# XMICRO-SERIAL_V1_0.net
KiCad netlist of a schematic drawn in EAGLE
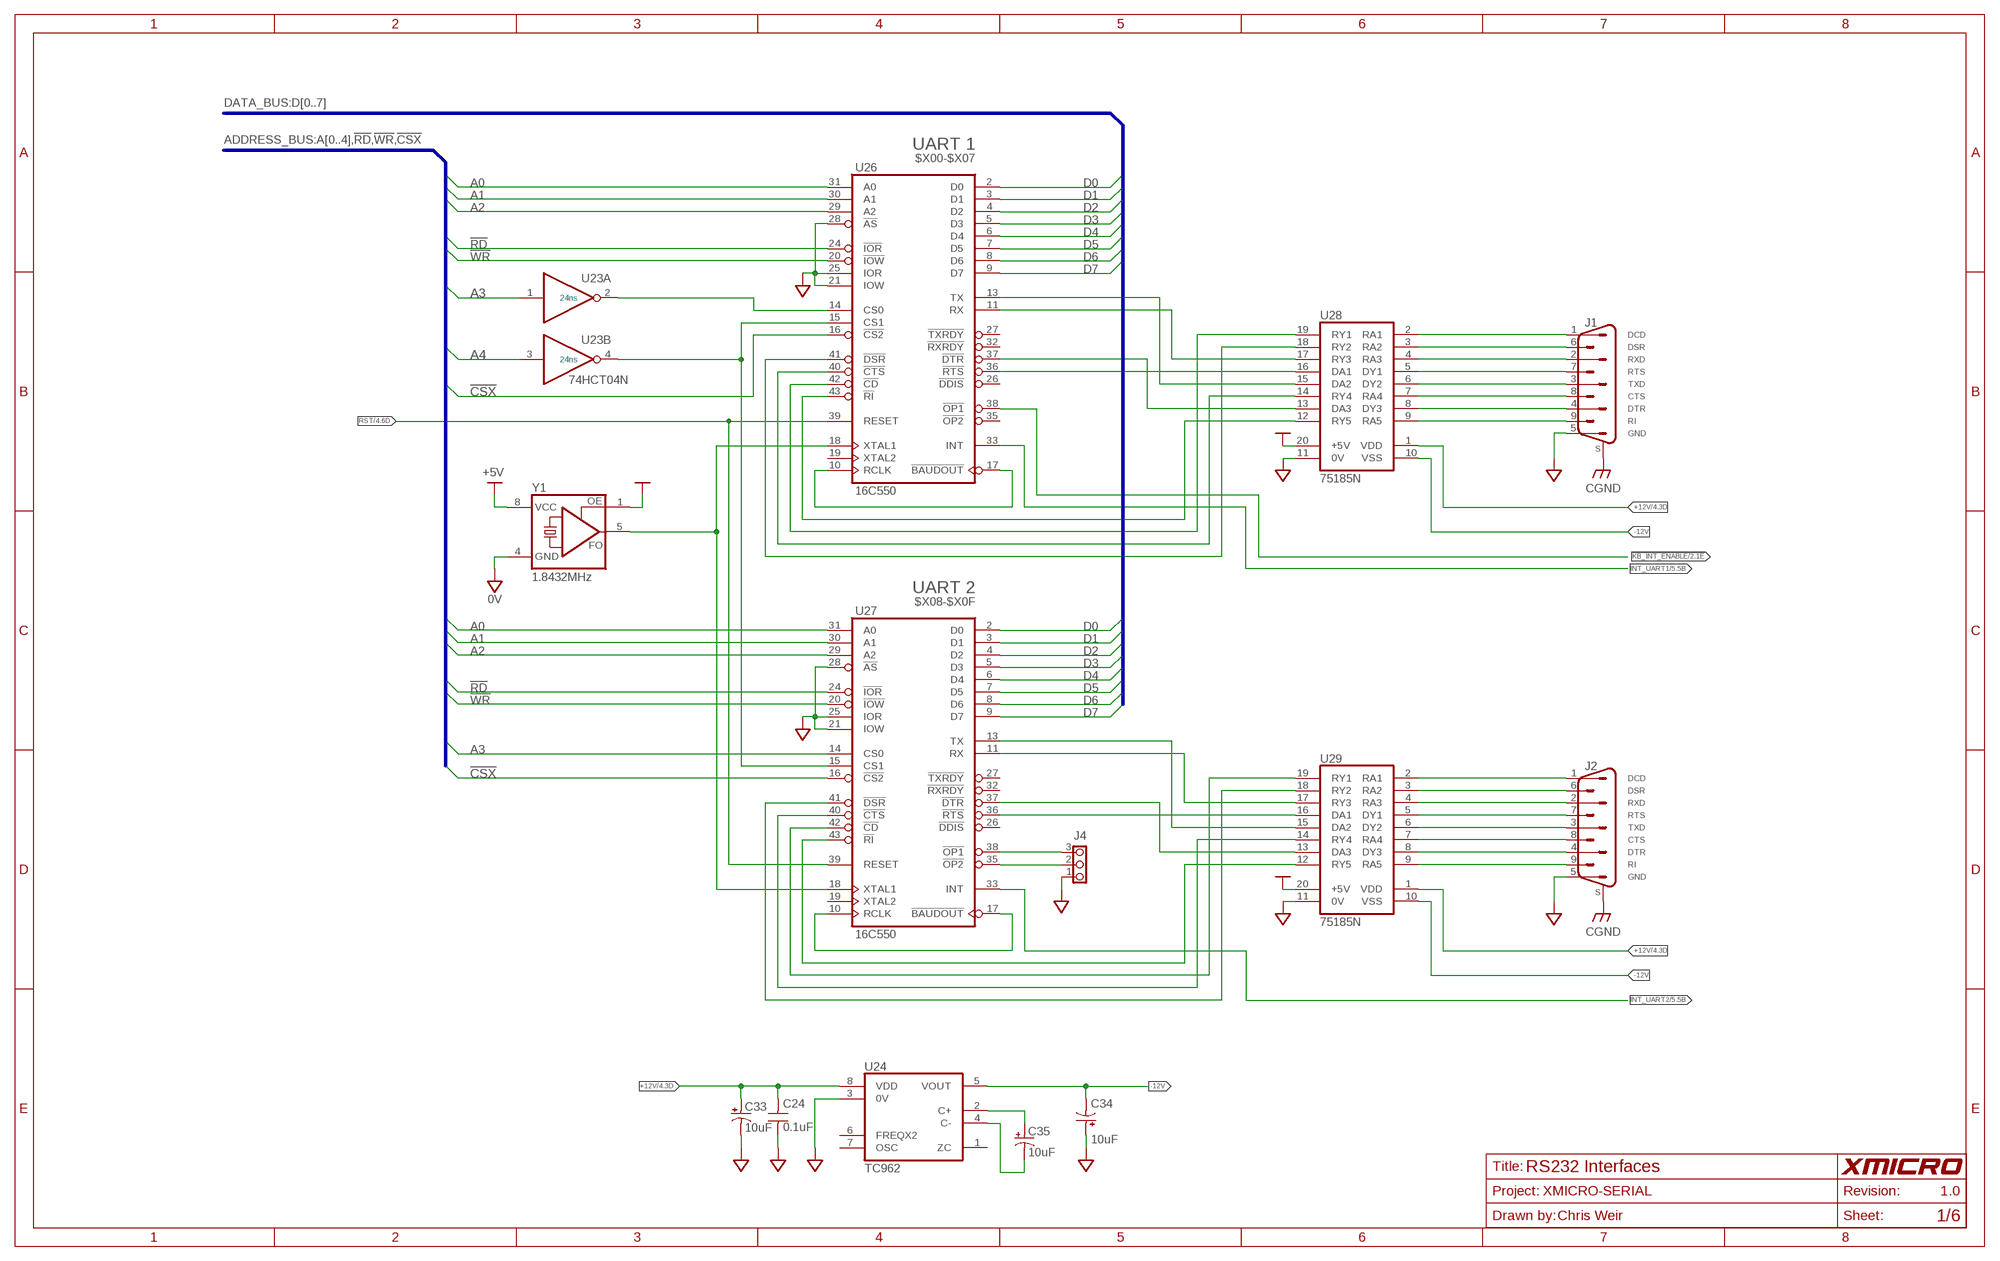
[diagram p0: schematic, sheet 1]
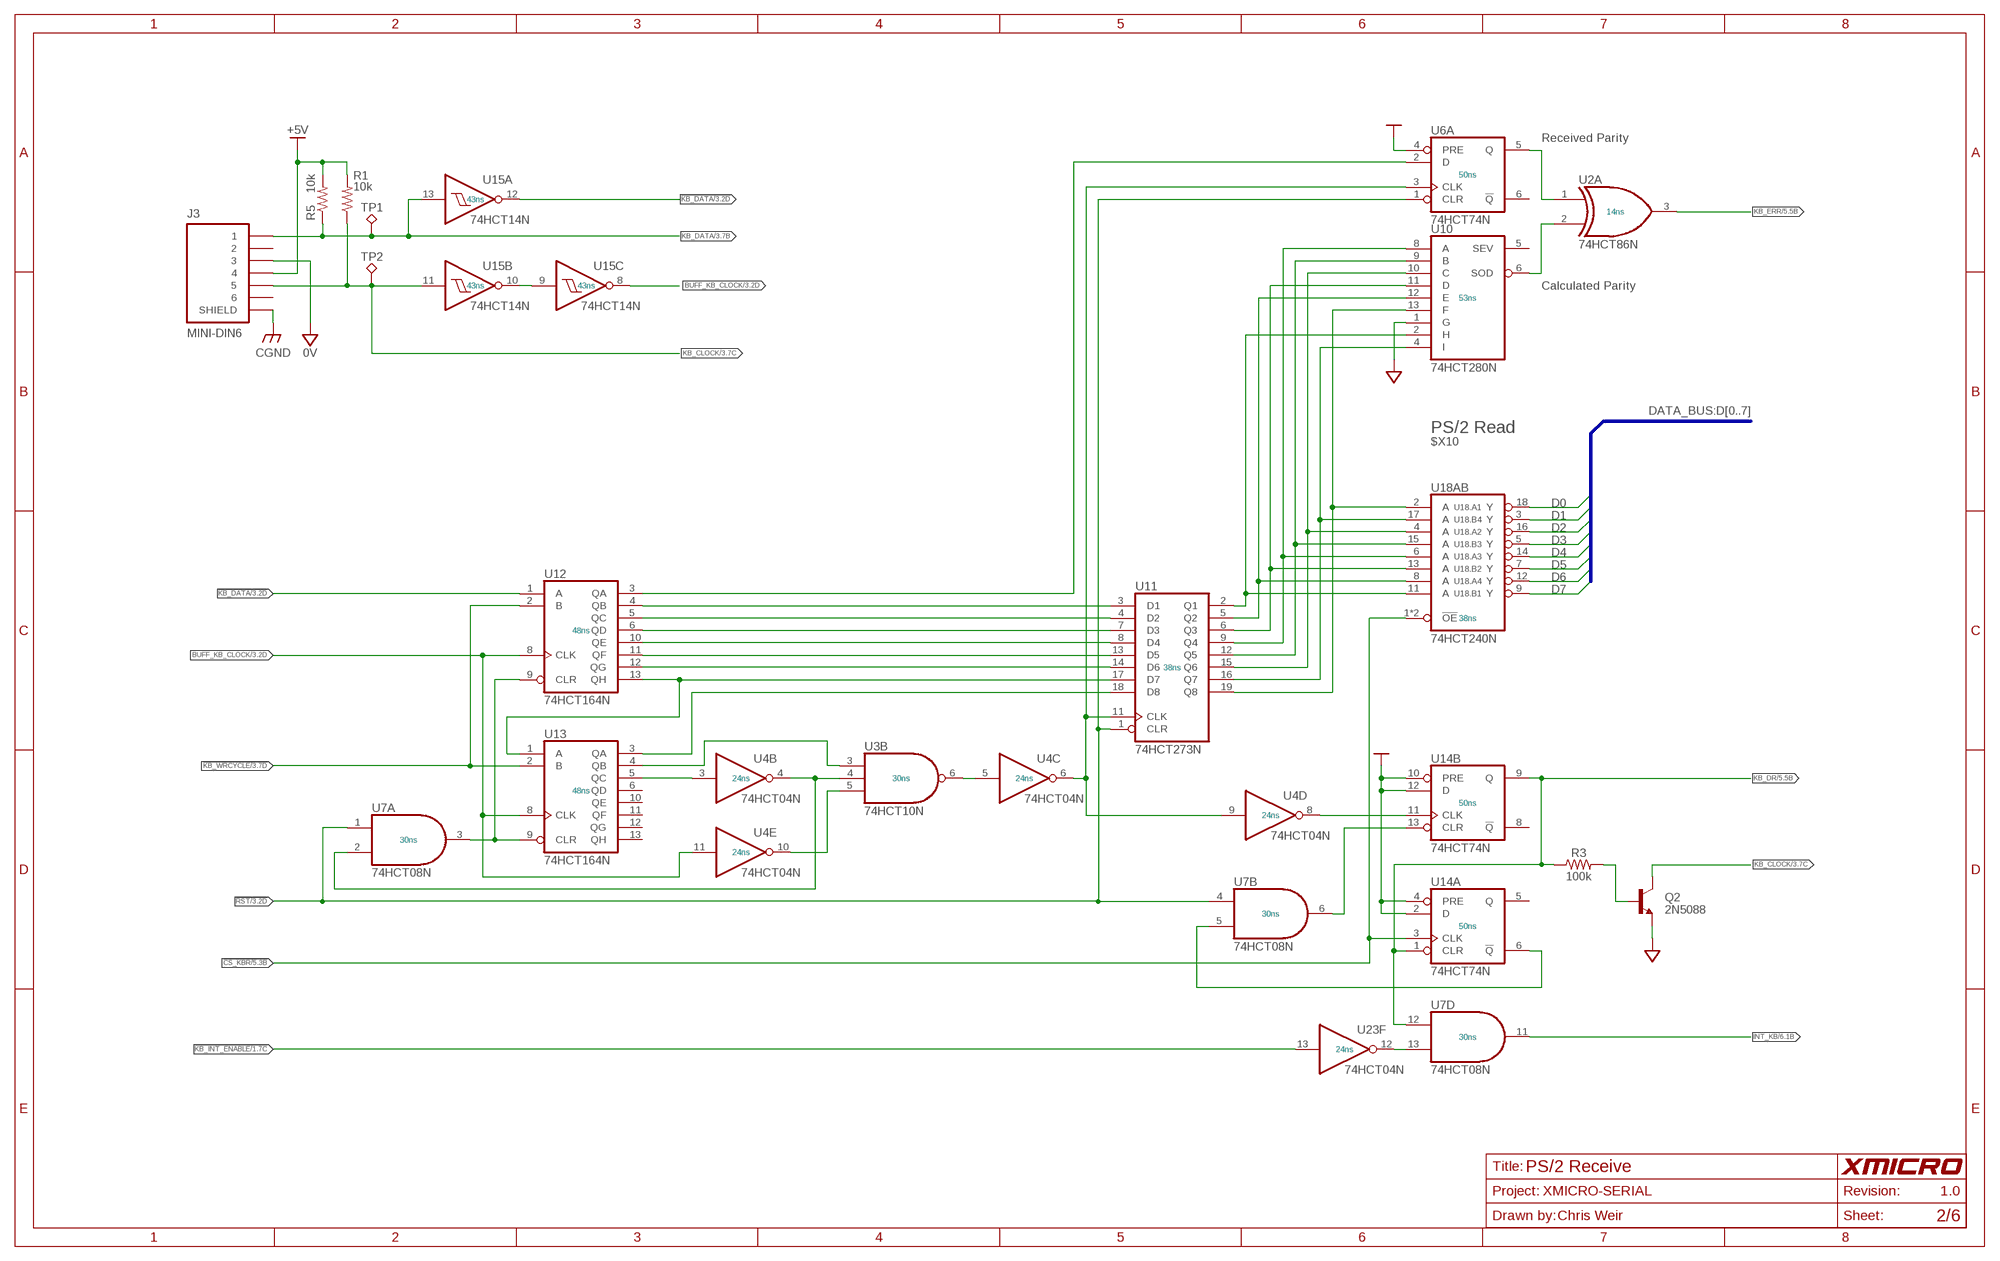
[diagram p1: schematic, sheet 2]
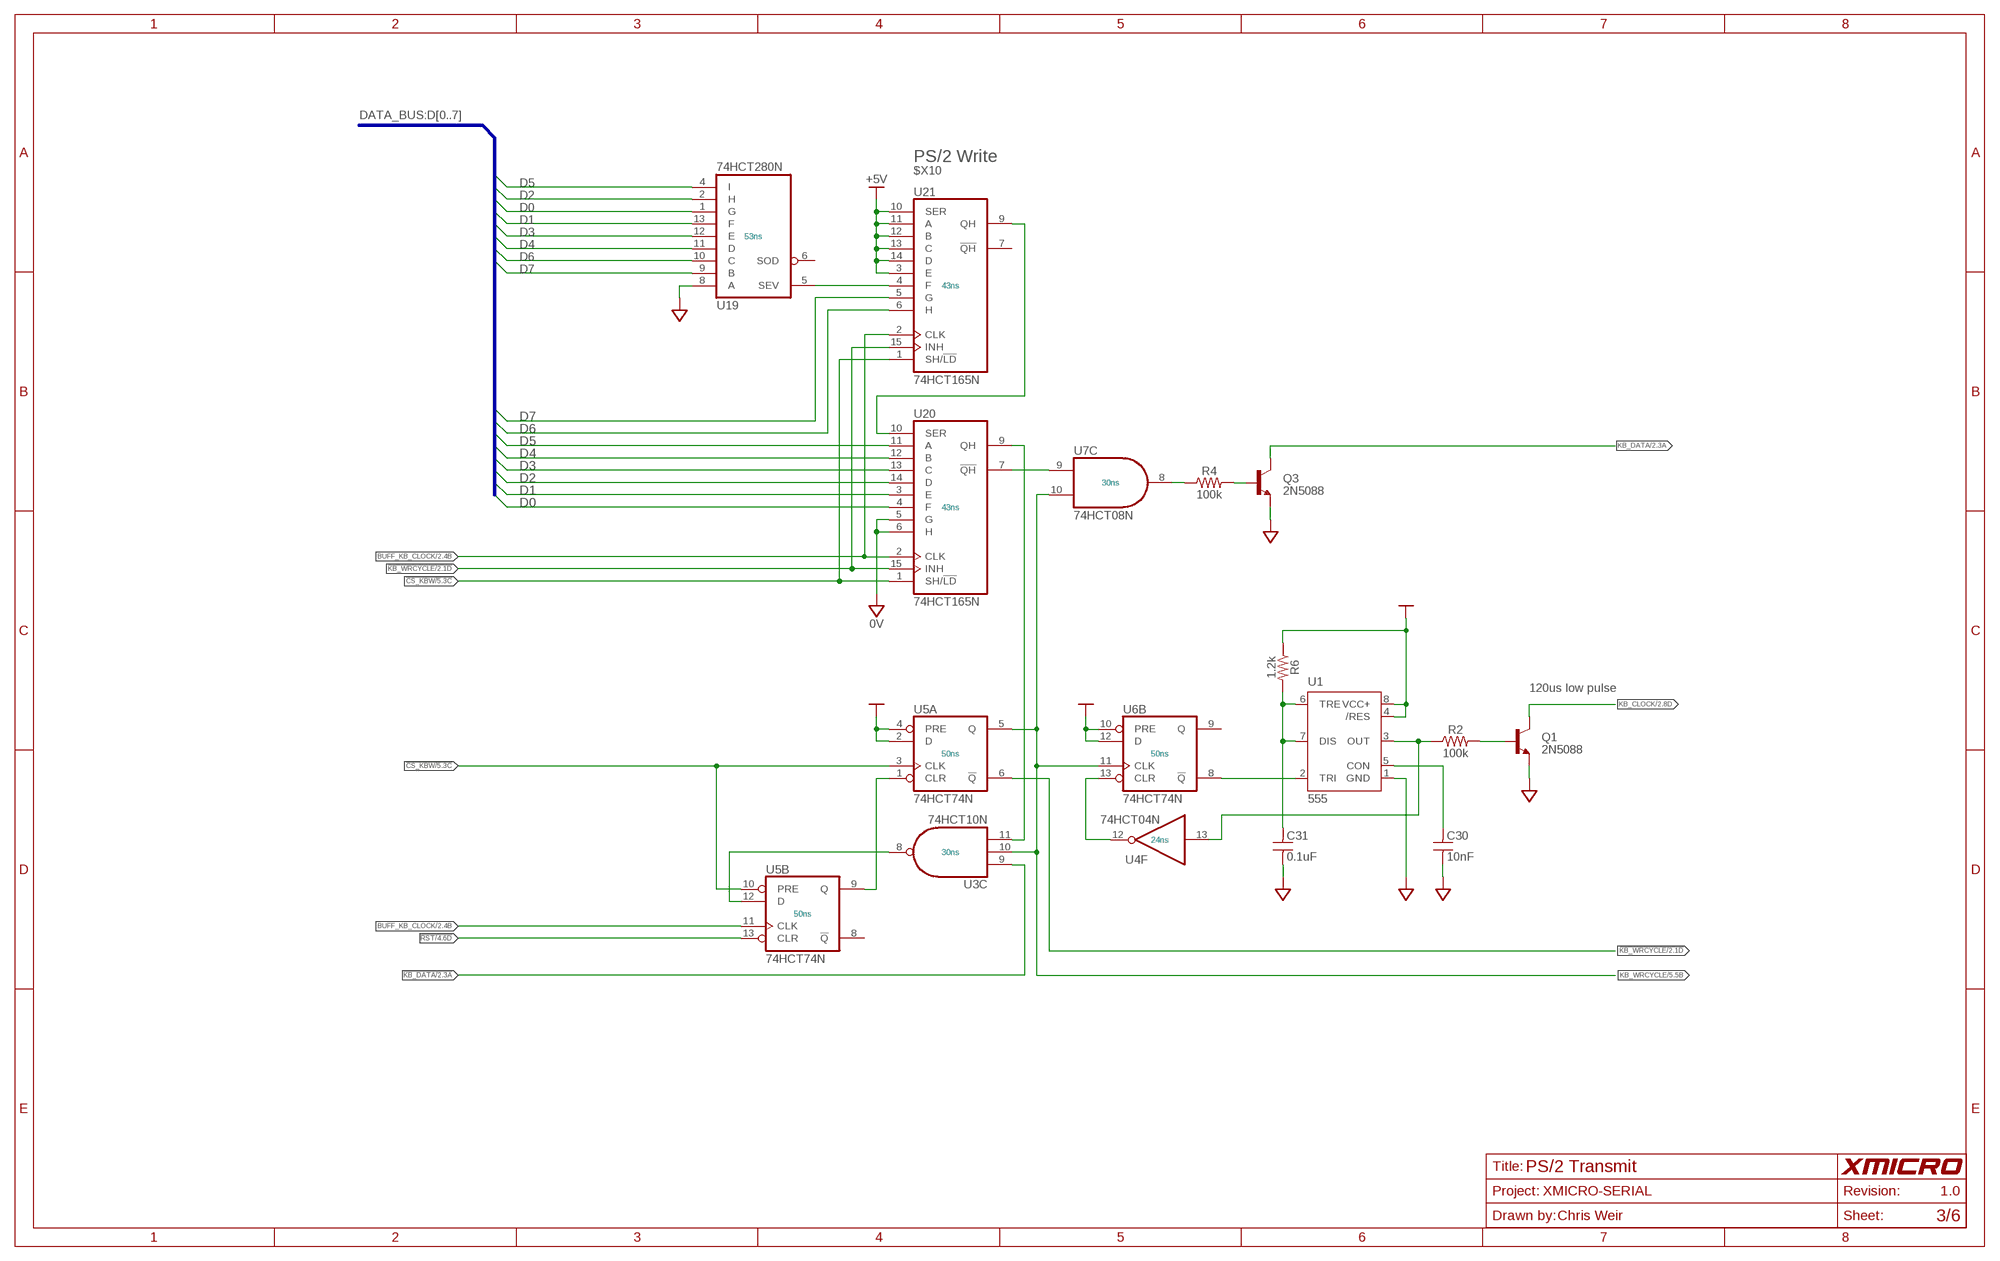
[diagram p2: schematic, sheet 3]
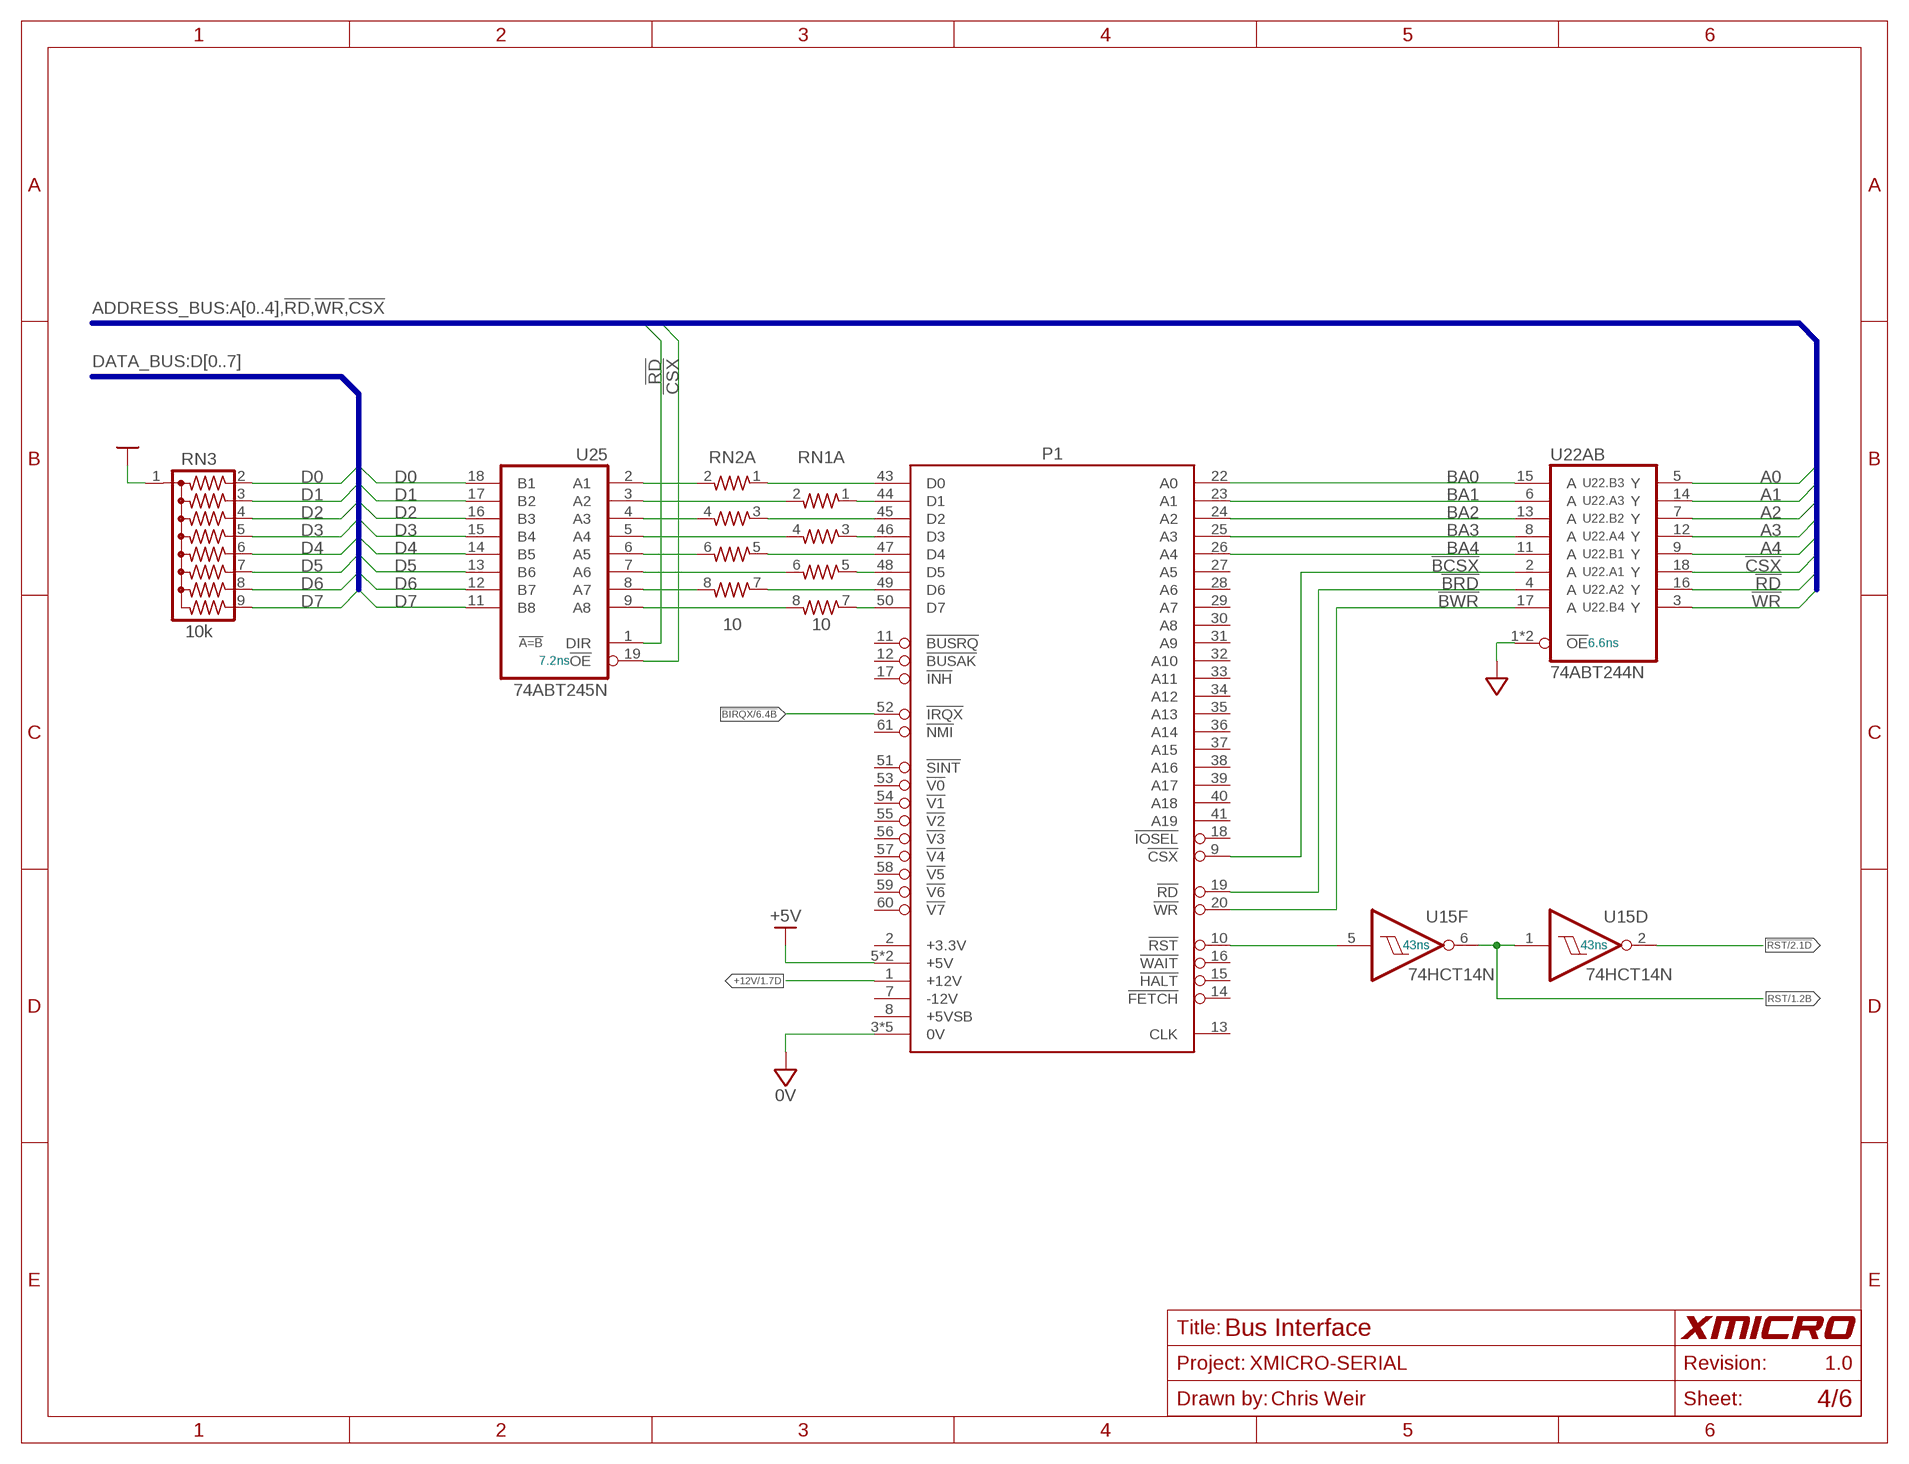
[diagram p3: schematic, sheet 4]
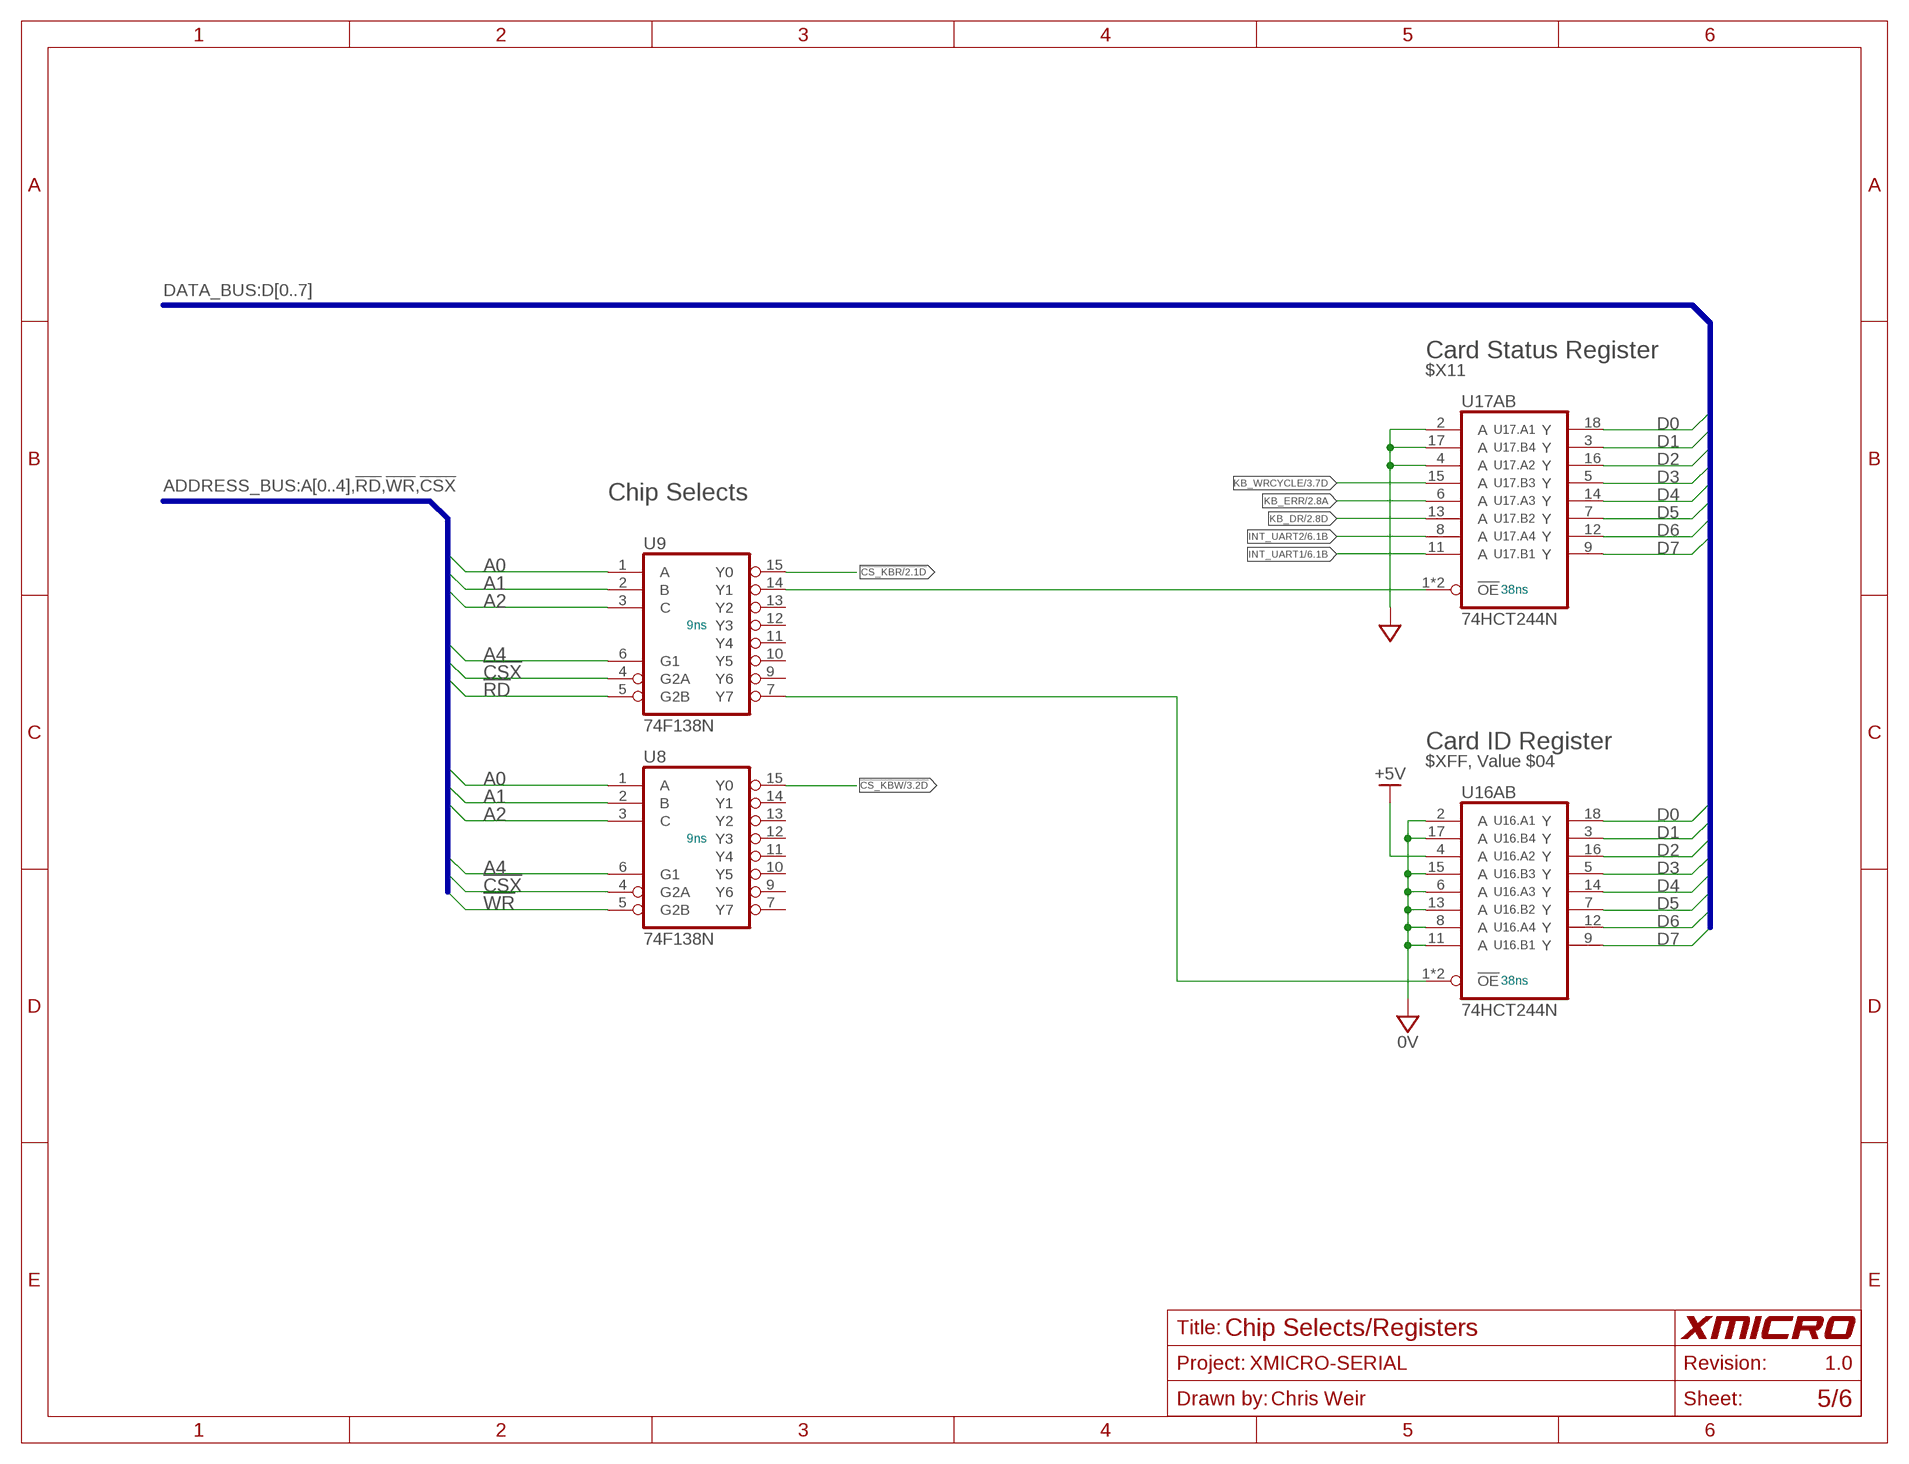
[diagram p4: schematic, sheet 5]
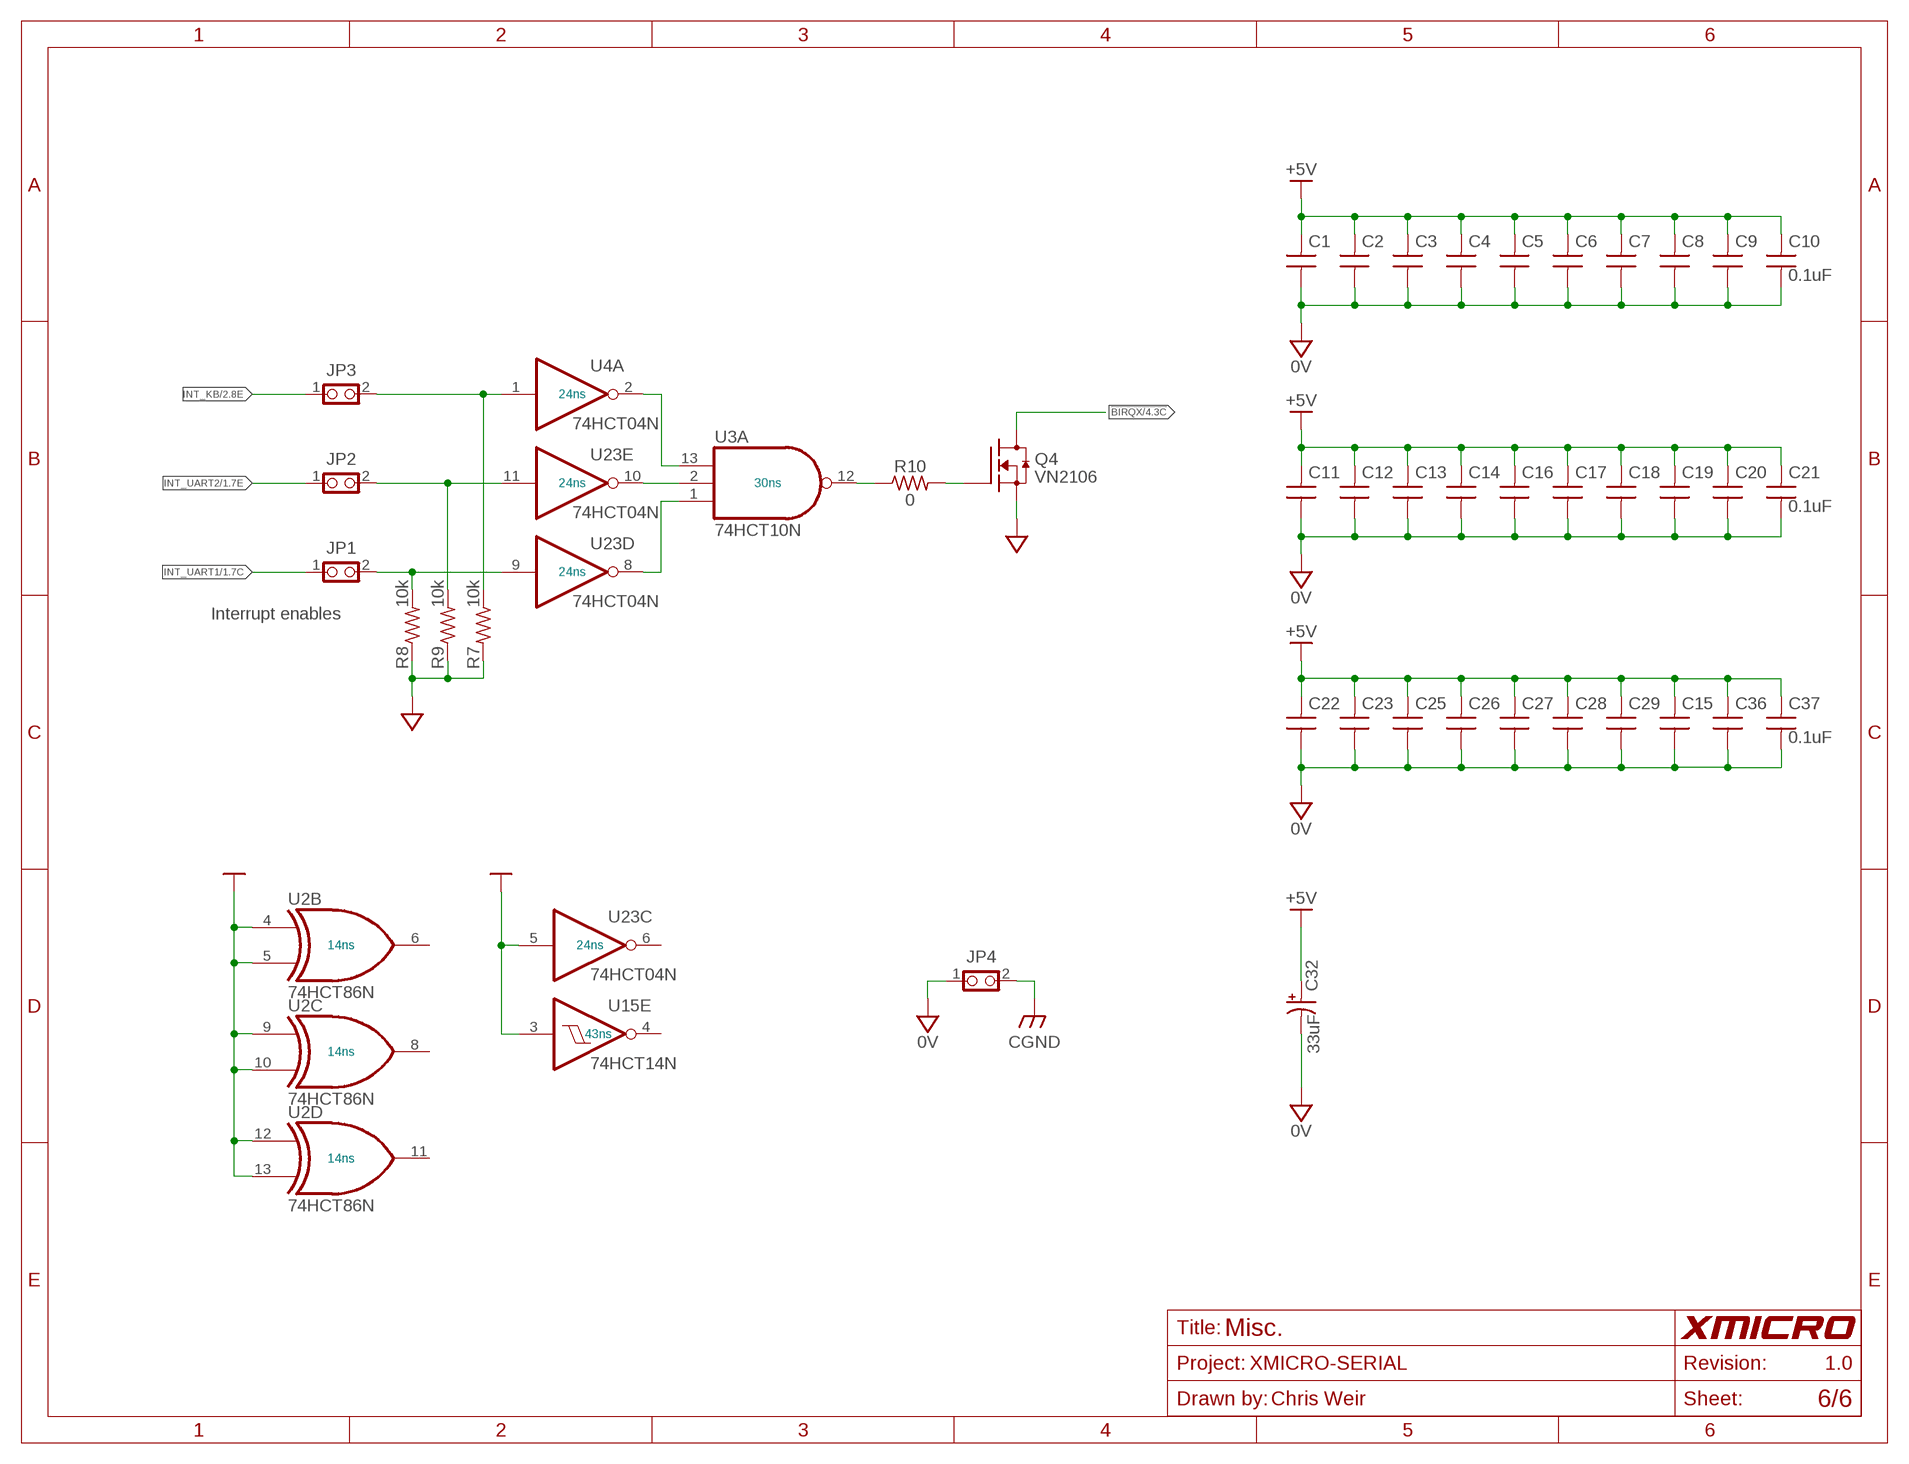
[diagram p5: schematic, sheet 6]

(export (version "E")
  (design (tool "Eeschema 10.0.6"))
  (components
    (comp (ref "C24")
      (value "0.1uF")
      (footprint "eagle-import:C025-024X044")
      (libsource (lib "eagle-import") (part "C-US025-024X044"))
    )
    (comp (ref "C33")
      (value "10uF")
      (footprint "eagle-import:E2,5-5")
      (libsource (lib "eagle-import") (part "CPOL-USE2.5-5"))
    )
    (comp (ref "C34")
      (value "10uF")
      (footprint "eagle-import:E2,5-5")
      (libsource (lib "eagle-import") (part "CPOL-USE2.5-5"))
    )
    (comp (ref "C35")
      (value "10uF")
      (footprint "eagle-import:E2,5-5")
      (libsource (lib "eagle-import") (part "CPOL-USE2.5-5"))
    )
    (comp (ref "J1")
      (value "DSUB-9M-PH")
      (footprint "eagle-import:DSUB-9M-H")
      (libsource (lib "eagle-import") (part "DSUB-9M-PH"))
    )
    (comp (ref "J2")
      (value "DSUB-9M-PH")
      (footprint "eagle-import:DSUB-9M-H")
      (libsource (lib "eagle-import") (part "DSUB-9M-PH"))
    )
    (comp (ref "J4")
      (value "1X3")
      (footprint "eagle-import:1X3")
      (libsource (lib "eagle-import") (part "1X3"))
    )
    (comp (ref "U23")
      (value "74HCT04N")
      (footprint "eagle-import:DIL14")
      (fields (field (name "TPD") "24ns") (field (name "TPD_1") "24ns"))
      (libsource (lib "eagle-import") (part "7404NHCT"))
    )
    (comp (ref "U24")
      (value "TC962")
      (footprint "eagle-import:DIL8")
      (libsource (lib "eagle-import") (part "TC962"))
    )
    (comp (ref "U26")
      (value "16C550")
      (footprint "eagle-import:S44")
      (libsource (lib "eagle-import") (part "16C550S44"))
    )
    (comp (ref "U27")
      (value "16C550")
      (footprint "eagle-import:S44")
      (libsource (lib "eagle-import") (part "16C550S44"))
    )
    (comp (ref "U28")
      (value "75185N")
      (footprint "eagle-import:DIL20")
      (libsource (lib "eagle-import") (part "75C185N"))
    )
    (comp (ref "U29")
      (value "75185N")
      (footprint "eagle-import:DIL20")
      (libsource (lib "eagle-import") (part "75C185N"))
    )
    (comp (ref "Y1")
      (value "1.8432MHz")
      (footprint "eagle-import:DIL08S")
      (libsource (lib "eagle-import") (part "OSC-OE"))
    )
    (comp (ref "C1")
      (value "0.1uF")
      (footprint "eagle-import:C025-024X044")
      (libsource (lib "eagle-import") (part "C-US025-024X044"))
    )
    (comp (ref "C2")
      (value "0.1uF")
      (footprint "eagle-import:C025-024X044")
      (libsource (lib "eagle-import") (part "C-US025-024X044"))
    )
    (comp (ref "C3")
      (value "0.1uF")
      (footprint "eagle-import:C025-024X044")
      (libsource (lib "eagle-import") (part "C-US025-024X044"))
    )
    (comp (ref "C4")
      (value "0.1uF")
      (footprint "eagle-import:C025-024X044")
      (libsource (lib "eagle-import") (part "C-US025-024X044"))
    )
    (comp (ref "C5")
      (value "0.1uF")
      (footprint "eagle-import:C025-024X044")
      (libsource (lib "eagle-import") (part "C-US025-024X044"))
    )
    (comp (ref "C6")
      (value "0.1uF")
      (footprint "eagle-import:C025-024X044")
      (libsource (lib "eagle-import") (part "C-US025-024X044"))
    )
    (comp (ref "C7")
      (value "0.1uF")
      (footprint "eagle-import:C025-024X044")
      (libsource (lib "eagle-import") (part "C-US025-024X044"))
    )
    (comp (ref "C8")
      (value "0.1uF")
      (footprint "eagle-import:C025-024X044")
      (libsource (lib "eagle-import") (part "C-US025-024X044"))
    )
    (comp (ref "C9")
      (value "0.1uF")
      (footprint "eagle-import:C025-024X044")
      (libsource (lib "eagle-import") (part "C-US025-024X044"))
    )
    (comp (ref "C10")
      (value "0.1uF")
      (footprint "eagle-import:C025-024X044")
      (libsource (lib "eagle-import") (part "C-US025-024X044"))
    )
    (comp (ref "C11")
      (value "0.1uF")
      (footprint "eagle-import:C025-024X044")
      (libsource (lib "eagle-import") (part "C-US025-024X044"))
    )
    (comp (ref "C12")
      (value "0.1uF")
      (footprint "eagle-import:C025-024X044")
      (libsource (lib "eagle-import") (part "C-US025-024X044"))
    )
    (comp (ref "C13")
      (value "0.1uF")
      (footprint "eagle-import:C025-024X044")
      (libsource (lib "eagle-import") (part "C-US025-024X044"))
    )
    (comp (ref "C14")
      (value "0.1uF")
      (footprint "eagle-import:C025-024X044")
      (libsource (lib "eagle-import") (part "C-US025-024X044"))
    )
    (comp (ref "C15")
      (value "0.1uF")
      (footprint "eagle-import:C025-024X044")
      (libsource (lib "eagle-import") (part "C-US025-024X044"))
    )
    (comp (ref "C16")
      (value "0.1uF")
      (footprint "eagle-import:C025-024X044")
      (libsource (lib "eagle-import") (part "C-US025-024X044"))
    )
    (comp (ref "C17")
      (value "0.1uF")
      (footprint "eagle-import:C025-024X044")
      (libsource (lib "eagle-import") (part "C-US025-024X044"))
    )
    (comp (ref "C18")
      (value "0.1uF")
      (footprint "eagle-import:C025-024X044")
      (libsource (lib "eagle-import") (part "C-US025-024X044"))
    )
    (comp (ref "C19")
      (value "0.1uF")
      (footprint "eagle-import:C025-024X044")
      (libsource (lib "eagle-import") (part "C-US025-024X044"))
    )
    (comp (ref "C20")
      (value "0.1uF")
      (footprint "eagle-import:C025-024X044")
      (libsource (lib "eagle-import") (part "C-US025-024X044"))
    )
    (comp (ref "C21")
      (value "0.1uF")
      (footprint "eagle-import:C025-024X044")
      (libsource (lib "eagle-import") (part "C-US025-024X044"))
    )
    (comp (ref "C22")
      (value "0.1uF")
      (footprint "eagle-import:C025-024X044")
      (libsource (lib "eagle-import") (part "C-US025-024X044"))
    )
    (comp (ref "C23")
      (value "0.1uF")
      (footprint "eagle-import:C025-024X044")
      (libsource (lib "eagle-import") (part "C-US025-024X044"))
    )
    (comp (ref "C25")
      (value "0.1uF")
      (footprint "eagle-import:C025-024X044")
      (libsource (lib "eagle-import") (part "C-US025-024X044"))
    )
    (comp (ref "C26")
      (value "0.1uF")
      (footprint "eagle-import:C025-024X044")
      (libsource (lib "eagle-import") (part "C-US025-024X044"))
    )
    (comp (ref "C27")
      (value "0.1uF")
      (footprint "eagle-import:C025-024X044")
      (libsource (lib "eagle-import") (part "C-US025-024X044"))
    )
    (comp (ref "C28")
      (value "0.1uF")
      (footprint "eagle-import:C025-024X044")
      (libsource (lib "eagle-import") (part "C-US025-024X044"))
    )
    (comp (ref "C29")
      (value "0.1uF")
      (footprint "eagle-import:C025-024X044")
      (libsource (lib "eagle-import") (part "C-US025-024X044"))
    )
    (comp (ref "C32")
      (value "33uF")
      (footprint "eagle-import:E2,5-6")
      (libsource (lib "eagle-import") (part "CPOL-USE2.5-6"))
    )
    (comp (ref "C36")
      (value "0.1uF")
      (footprint "eagle-import:C025-024X044")
      (libsource (lib "eagle-import") (part "C-US025-024X044"))
    )
    (comp (ref "C37")
      (value "0.1uF")
      (footprint "eagle-import:C025-024X044")
      (libsource (lib "eagle-import") (part "C-US025-024X044"))
    )
    (comp (ref "JP1")
      (value "1X2-THRU")
      (footprint "eagle-import:1X2")
      (libsource (lib "eagle-import") (part "1X2-THRU"))
    )
    (comp (ref "JP2")
      (value "1X2-THRU")
      (footprint "eagle-import:1X2")
      (libsource (lib "eagle-import") (part "1X2-THRU"))
    )
    (comp (ref "JP3")
      (value "1X2-THRU")
      (footprint "eagle-import:1X2")
      (libsource (lib "eagle-import") (part "1X2-THRU"))
    )
    (comp (ref "JP4")
      (value "1X2-THRU")
      (footprint "eagle-import:1X2")
      (libsource (lib "eagle-import") (part "1X2-THRU"))
    )
    (comp (ref "Q4")
      (value "VN2106")
      (footprint "eagle-import:TO92")
      (libsource (lib "eagle-import") (part "VN2106"))
    )
    (comp (ref "R7")
      (value "10k")
      (footprint "eagle-import:0207_10")
      (libsource (lib "eagle-import") (part "R-US_0207/10"))
    )
    (comp (ref "R8")
      (value "10k")
      (footprint "eagle-import:0207_10")
      (libsource (lib "eagle-import") (part "R-US_0207/10"))
    )
    (comp (ref "R9")
      (value "10k")
      (footprint "eagle-import:0207_10")
      (libsource (lib "eagle-import") (part "R-US_0207/10"))
    )
    (comp (ref "R10")
      (value "0")
      (footprint "eagle-import:0207_10")
      (libsource (lib "eagle-import") (part "resistor_R-US_0207/10"))
    )
    (comp (ref "U2")
      (value "74HCT86N")
      (footprint "eagle-import:DIL14")
      (fields (field (name "TPD") "14ns"))
      (libsource (lib "eagle-import") (part "7486NHCT"))
    )
    (comp (ref "U3")
      (value "74HCT10N")
      (footprint "eagle-import:DIL14")
      (fields (field (name "TPD") "30ns") (field (name "TPD_1") "30ns"))
      (libsource (lib "eagle-import") (part "7410NHCT"))
    )
    (comp (ref "U4")
      (value "74HCT04N")
      (footprint "eagle-import:DIL14")
      (fields (field (name "TPD") "24ns"))
      (libsource (lib "eagle-import") (part "7404NHCT"))
    )
    (comp (ref "U15")
      (value "74HCT14N")
      (footprint "eagle-import:DIL14")
      (fields (field (name "TPD") "43ns"))
      (libsource (lib "eagle-import") (part "7414NHCT"))
    )
    (comp (ref "U8")
      (value "74F138N")
      (footprint "eagle-import:DIL16")
      (libsource (lib "eagle-import") (part "74138NF"))
    )
    (comp (ref "U9")
      (value "74F138N")
      (footprint "eagle-import:DIL16")
      (libsource (lib "eagle-import") (part "74138NF"))
    )
    (comp (ref "U16")
      (value "74HCT244N")
      (footprint "eagle-import:DIL20")
      (libsource (lib "eagle-import") (part "74244-1SNHCT"))
    )
    (comp (ref "U17")
      (value "74HCT244N")
      (footprint "eagle-import:DIL20")
      (libsource (lib "eagle-import") (part "74244-1SNHCT"))
    )
    (comp (ref "C30")
      (value "10nF")
      (footprint "eagle-import:C025-024X044")
      (libsource (lib "eagle-import") (part "C-US025-024X044"))
    )
    (comp (ref "C31")
      (value "0.1uF")
      (footprint "eagle-import:C025-024X044")
      (libsource (lib "eagle-import") (part "C-US025-024X044"))
    )
    (comp (ref "Q1")
      (value "2N5088")
      (footprint "eagle-import:TO92")
      (libsource (lib "eagle-import") (part "2N5088"))
    )
    (comp (ref "Q3")
      (value "2N5088")
      (footprint "eagle-import:TO92")
      (libsource (lib "eagle-import") (part "2N5088"))
    )
    (comp (ref "R2")
      (value "100k")
      (footprint "eagle-import:0207_10")
      (libsource (lib "eagle-import") (part "R-US_0207/10"))
    )
    (comp (ref "R4")
      (value "100k")
      (footprint "eagle-import:0207_10")
      (libsource (lib "eagle-import") (part "R-US_0207/10"))
    )
    (comp (ref "R6")
      (value "1.2k")
      (footprint "eagle-import:0207_10")
      (libsource (lib "eagle-import") (part "R-US_0207/10"))
    )
    (comp (ref "U1")
      (value "555")
      (footprint "eagle-import:DIL-08")
      (fields (field (name "MF") "Arrow Electronics") (field (name "MPN") "NE555N"))
      (libsource (lib "eagle-import") (part "NE555"))
    )
    (comp (ref "U5")
      (value "74HCT74N")
      (footprint "eagle-import:DIL14")
      (fields (field (name "TPD") "50ns"))
      (libsource (lib "eagle-import") (part "7474NHCT"))
    )
    (comp (ref "U6")
      (value "74HCT74N")
      (footprint "eagle-import:DIL14")
      (fields (field (name "TPD") "50ns"))
      (libsource (lib "eagle-import") (part "7474NHCT"))
    )
    (comp (ref "U7")
      (value "74HCT08N")
      (footprint "eagle-import:DIL14")
      (fields (field (name "TPD") "30ns"))
      (libsource (lib "eagle-import") (part "7408NHCT"))
    )
    (comp (ref "U19")
      (value "74HCT280N")
      (footprint "eagle-import:DIL14")
      (libsource (lib "eagle-import") (part "74280NHCT"))
    )
    (comp (ref "U20")
      (value "74HCT165N")
      (footprint "eagle-import:DIL16")
      (libsource (lib "eagle-import") (part "74165NHCT"))
    )
    (comp (ref "U21")
      (value "74HCT165N")
      (footprint "eagle-import:DIL16")
      (libsource (lib "eagle-import") (part "74165NHCT"))
    )
    (comp (ref "J3")
      (value "MINI-DIN6")
      (footprint "eagle-import:MINI-DIN6")
      (libsource (lib "eagle-import") (part "MINI-DIN6"))
    )
    (comp (ref "Q2")
      (value "2N5088")
      (footprint "eagle-import:TO92")
      (libsource (lib "eagle-import") (part "2N5088"))
    )
    (comp (ref "R1")
      (value "10k")
      (footprint "eagle-import:0207_10")
      (libsource (lib "eagle-import") (part "R-US_0207/10"))
    )
    (comp (ref "R3")
      (value "100k")
      (footprint "eagle-import:0207_10")
      (libsource (lib "eagle-import") (part "R-US_0207/10"))
    )
    (comp (ref "R5")
      (value "10k")
      (footprint "eagle-import:0207_10")
      (libsource (lib "eagle-import") (part "R-US_0207/10"))
    )
    (comp (ref "TP1")
      (value "TP-040")
      (footprint "eagle-import:TP-040")
      (libsource (lib "eagle-import") (part "TP-040"))
    )
    (comp (ref "TP2")
      (value "TP-040")
      (footprint "eagle-import:TP-040")
      (libsource (lib "eagle-import") (part "TP-040"))
    )
    (comp (ref "U10")
      (value "74HCT280N")
      (footprint "eagle-import:DIL14")
      (libsource (lib "eagle-import") (part "74280NHCT"))
    )
    (comp (ref "U11")
      (value "74HCT273N")
      (footprint "eagle-import:DIL20")
      (libsource (lib "eagle-import") (part "74273NHCT"))
    )
    (comp (ref "U12")
      (value "74HCT164N")
      (footprint "eagle-import:DIL14")
      (libsource (lib "eagle-import") (part "74164NHCT"))
    )
    (comp (ref "U13")
      (value "74HCT164N")
      (footprint "eagle-import:DIL14")
      (libsource (lib "eagle-import") (part "74164NHCT"))
    )
    (comp (ref "U14")
      (value "74HCT74N")
      (footprint "eagle-import:DIL14")
      (fields (field (name "TPD") "50ns"))
      (libsource (lib "eagle-import") (part "7474NHCT"))
    )
    (comp (ref "U18")
      (value "74HCT240N")
      (footprint "eagle-import:DIL20")
      (libsource (lib "eagle-import") (part "74240-1SNHCT"))
    )
    (comp (ref "P1")
      (value "XMICRO-BUS-EDGE")
      (footprint "eagle-import:EDGE62M")
      (libsource (lib "eagle-import") (part "XMICRO-BUS-EDGE"))
    )
    (comp (ref "RN1")
      (value "10")
      (footprint "eagle-import:SIL8")
      (libsource (lib "eagle-import") (part "E4R"))
    )
    (comp (ref "RN2")
      (value "10")
      (footprint "eagle-import:SIL8")
      (libsource (lib "eagle-import") (part "E4R"))
    )
    (comp (ref "RN3")
      (value "10k")
      (footprint "eagle-import:SIL9")
      (libsource (lib "eagle-import") (part "G08R"))
    )
    (comp (ref "U22")
      (value "74ABT244N")
      (footprint "eagle-import:DIL20")
      (libsource (lib "eagle-import") (part "74244-1SNABT"))
    )
    (comp (ref "U25")
      (value "74ABT245N")
      (footprint "eagle-import:DIL20")
      (libsource (lib "eagle-import") (part "74245NABT"))
    )
  )
  (nets
    (net (code "41") (name "+5V") (class "Default")
      (node (ref "C1") (pin "1") (pinfunction "1_1") (pintype "passive"))
      (node (ref "C10") (pin "1") (pinfunction "1_1") (pintype "passive"))
      (node (ref "C11") (pin "1") (pinfunction "1_1") (pintype "passive"))
      (node (ref "C12") (pin "1") (pinfunction "1_1") (pintype "passive"))
      (node (ref "C13") (pin "1") (pinfunction "1_1") (pintype "passive"))
      (node (ref "C14") (pin "1") (pinfunction "1_1") (pintype "passive"))
      (node (ref "C15") (pin "1") (pinfunction "1_1") (pintype "passive"))
      (node (ref "C16") (pin "1") (pinfunction "1_1") (pintype "passive"))
      (node (ref "C17") (pin "1") (pinfunction "1_1") (pintype "passive"))
      (node (ref "C18") (pin "1") (pinfunction "1_1") (pintype "passive"))
      (node (ref "C19") (pin "1") (pinfunction "1_1") (pintype "passive"))
      (node (ref "C2") (pin "1") (pinfunction "1_1") (pintype "passive"))
      (node (ref "C20") (pin "1") (pinfunction "1_1") (pintype "passive"))
      (node (ref "C21") (pin "1") (pinfunction "1_1") (pintype "passive"))
      (node (ref "C22") (pin "1") (pinfunction "1_1") (pintype "passive"))
      (node (ref "C23") (pin "1") (pinfunction "1_1") (pintype "passive"))
      (node (ref "C25") (pin "1") (pinfunction "1_1") (pintype "passive"))
      (node (ref "C26") (pin "1") (pinfunction "1_1") (pintype "passive"))
      (node (ref "C27") (pin "1") (pinfunction "1_1") (pintype "passive"))
      (node (ref "C28") (pin "1") (pinfunction "1_1") (pintype "passive"))
      (node (ref "C29") (pin "1") (pinfunction "1_1") (pintype "passive"))
      (node (ref "C3") (pin "1") (pinfunction "1_1") (pintype "passive"))
      (node (ref "C32") (pin "+") (pinfunction "+_+") (pintype "passive"))
      (node (ref "C36") (pin "1") (pinfunction "1_1") (pintype "passive"))
      (node (ref "C37") (pin "1") (pinfunction "1_1") (pintype "passive"))
      (node (ref "C4") (pin "1") (pinfunction "1_1") (pintype "passive"))
      (node (ref "C5") (pin "1") (pinfunction "1_1") (pintype "passive"))
      (node (ref "C6") (pin "1") (pinfunction "1_1") (pintype "passive"))
      (node (ref "C7") (pin "1") (pinfunction "1_1") (pintype "passive"))
      (node (ref "C8") (pin "1") (pinfunction "1_1") (pintype "passive"))
      (node (ref "C9") (pin "1") (pinfunction "1_1") (pintype "passive"))
      (node (ref "J3") (pin "4") (pinfunction "4_4") (pintype "bidirectional"))
      (node (ref "P1") (pin "5") (pinfunction "+5V_5") (pintype "bidirectional"))
      (node (ref "P1") (pin "6") (pinfunction "+5V_6") (pintype "bidirectional"))
      (node (ref "R1") (pin "2") (pinfunction "2_2") (pintype "passive"))
      (node (ref "R5") (pin "2") (pinfunction "2_2") (pintype "passive"))
      (node (ref "R6") (pin "1") (pinfunction "1_1") (pintype "passive"))
      (node (ref "RN3") (pin "1") (pinfunction "1_1") (pintype "passive"))
      (node (ref "U1") (pin "4") (pinfunction "/RES_4") (pintype "input"))
      (node (ref "U1") (pin "8") (pinfunction "VCC+_8") (pintype "power_in"))
      (node (ref "U14") (pin "10") (pinfunction "PRE_10") (pintype "input"))
      (node (ref "U14") (pin "12") (pinfunction "D_12") (pintype "input"))
      (node (ref "U14") (pin "2") (pinfunction "D_2") (pintype "input"))
      (node (ref "U14") (pin "4") (pinfunction "PRE_4") (pintype "input"))
      (node (ref "U15") (pin "3") (pinfunction "I_3") (pintype "input"))
      (node (ref "U16") (pin "4") (pinfunction "A_4") (pintype "input"))
      (node (ref "U2") (pin "10") (pinfunction "I1_10") (pintype "input"))
      (node (ref "U2") (pin "12") (pinfunction "I0_12") (pintype "input"))
      (node (ref "U2") (pin "13") (pinfunction "I1_13") (pintype "input"))
      (node (ref "U2") (pin "4") (pinfunction "I0_4") (pintype "input"))
      (node (ref "U2") (pin "5") (pinfunction "I1_5") (pintype "input"))
      (node (ref "U2") (pin "9") (pinfunction "I0_9") (pintype "input"))
      (node (ref "U21") (pin "10") (pinfunction "SER_10") (pintype "input"))
      (node (ref "U21") (pin "11") (pinfunction "A_11") (pintype "input"))
      (node (ref "U21") (pin "12") (pinfunction "B_12") (pintype "input"))
      (node (ref "U21") (pin "13") (pinfunction "C_13") (pintype "input"))
      (node (ref "U21") (pin "14") (pinfunction "D_14") (pintype "input"))
      (node (ref "U21") (pin "3") (pinfunction "E_3") (pintype "input"))
      (node (ref "U23") (pin "5") (pinfunction "I_5") (pintype "input"))
      (node (ref "U28") (pin "20") (pinfunction "+5V_20") (pintype "power_in"))
      (node (ref "U29") (pin "20") (pinfunction "+5V_20") (pintype "power_in"))
      (node (ref "U5") (pin "2") (pinfunction "D_2") (pintype "input"))
      (node (ref "U5") (pin "4") (pinfunction "PRE_4") (pintype "input"))
      (node (ref "U6") (pin "10") (pinfunction "PRE_10") (pintype "input"))
      (node (ref "U6") (pin "12") (pinfunction "D_12") (pintype "input"))
      (node (ref "U6") (pin "4") (pinfunction "PRE_4") (pintype "input"))
      (node (ref "Y1") (pin "1") (pinfunction "OE_1") (pintype "input"))
      (node (ref "Y1") (pin "8") (pinfunction "+5V_8") (pintype "power_in"))
    )
    (net (code "42") (name "+12V") (class "Default")
      (node (ref "C24") (pin "1") (pinfunction "1_1") (pintype "passive"))
      (node (ref "C33") (pin "+") (pinfunction "+_+") (pintype "passive"))
      (node (ref "P1") (pin "1") (pinfunction "+12V_1") (pintype "bidirectional"))
      (node (ref "U24") (pin "8") (pinfunction "VDD_8") (pintype "input"))
      (node (ref "U28") (pin "1") (pinfunction "VDD_1") (pintype "power_in"))
      (node (ref "U29") (pin "1") (pinfunction "VDD_1") (pintype "power_in"))
    )
    (net (code "43") (name "-12V") (class "Default")
      (node (ref "C34") (pin "-") (pinfunction "-_-") (pintype "passive"))
      (node (ref "U24") (pin "5") (pinfunction "VOUT_5") (pintype "output"))
      (node (ref "U28") (pin "10") (pinfunction "VSS_10") (pintype "power_in"))
      (node (ref "U29") (pin "10") (pinfunction "VSS_10") (pintype "power_in"))
    )
    (net (code "52") (name "0V") (class "Default")
      (node (ref "C1") (pin "2") (pinfunction "2_2") (pintype "passive"))
      (node (ref "C10") (pin "2") (pinfunction "2_2") (pintype "passive"))
      (node (ref "C11") (pin "2") (pinfunction "2_2") (pintype "passive"))
      (node (ref "C12") (pin "2") (pinfunction "2_2") (pintype "passive"))
      (node (ref "C13") (pin "2") (pinfunction "2_2") (pintype "passive"))
      (node (ref "C14") (pin "2") (pinfunction "2_2") (pintype "passive"))
      (node (ref "C15") (pin "2") (pinfunction "2_2") (pintype "passive"))
      (node (ref "C16") (pin "2") (pinfunction "2_2") (pintype "passive"))
      (node (ref "C17") (pin "2") (pinfunction "2_2") (pintype "passive"))
      (node (ref "C18") (pin "2") (pinfunction "2_2") (pintype "passive"))
      (node (ref "C19") (pin "2") (pinfunction "2_2") (pintype "passive"))
      (node (ref "C2") (pin "2") (pinfunction "2_2") (pintype "passive"))
      (node (ref "C20") (pin "2") (pinfunction "2_2") (pintype "passive"))
      (node (ref "C21") (pin "2") (pinfunction "2_2") (pintype "passive"))
      (node (ref "C22") (pin "2") (pinfunction "2_2") (pintype "passive"))
      (node (ref "C23") (pin "2") (pinfunction "2_2") (pintype "passive"))
      (node (ref "C24") (pin "2") (pinfunction "2_2") (pintype "passive"))
      (node (ref "C25") (pin "2") (pinfunction "2_2") (pintype "passive"))
      (node (ref "C26") (pin "2") (pinfunction "2_2") (pintype "passive"))
      (node (ref "C27") (pin "2") (pinfunction "2_2") (pintype "passive"))
      (node (ref "C28") (pin "2") (pinfunction "2_2") (pintype "passive"))
      (node (ref "C29") (pin "2") (pinfunction "2_2") (pintype "passive"))
      (node (ref "C3") (pin "2") (pinfunction "2_2") (pintype "passive"))
      (node (ref "C30") (pin "2") (pinfunction "2_2") (pintype "passive"))
      (node (ref "C31") (pin "2") (pinfunction "2_2") (pintype "passive"))
      (node (ref "C32") (pin "-") (pinfunction "-_-") (pintype "passive"))
      (node (ref "C33") (pin "-") (pinfunction "-_-") (pintype "passive"))
      (node (ref "C34") (pin "+") (pinfunction "+_+") (pintype "passive"))
      (node (ref "C36") (pin "2") (pinfunction "2_2") (pintype "passive"))
      (node (ref "C37") (pin "2") (pinfunction "2_2") (pintype "passive"))
      (node (ref "C4") (pin "2") (pinfunction "2_2") (pintype "passive"))
      (node (ref "C5") (pin "2") (pinfunction "2_2") (pintype "passive"))
      (node (ref "C6") (pin "2") (pinfunction "2_2") (pintype "passive"))
      (node (ref "C7") (pin "2") (pinfunction "2_2") (pintype "passive"))
      (node (ref "C8") (pin "2") (pinfunction "2_2") (pintype "passive"))
      (node (ref "C9") (pin "2") (pinfunction "2_2") (pintype "passive"))
      (node (ref "J1") (pin "5") (pinfunction "5_5") (pintype "passive"))
      (node (ref "J2") (pin "5") (pinfunction "5_5") (pintype "passive"))
      (node (ref "J3") (pin "3") (pinfunction "3_3") (pintype "bidirectional"))
      (node (ref "J4") (pin "1") (pinfunction "1_1") (pintype "passive"))
      (node (ref "JP4") (pin "1") (pinfunction "1_1") (pintype "passive"))
      (node (ref "P1") (pin "21") (pinfunction "0V_21") (pintype "bidirectional"))
      (node (ref "P1") (pin "3") (pinfunction "0V_3") (pintype "bidirectional"))
      (node (ref "P1") (pin "4") (pinfunction "0V_4") (pintype "bidirectional"))
      (node (ref "P1") (pin "42") (pinfunction "0V_42") (pintype "bidirectional"))
      (node (ref "P1") (pin "62") (pinfunction "0V_62") (pintype "bidirectional"))
      (node (ref "Q1") (pin "1") (pinfunction "E_1") (pintype "passive"))
      (node (ref "Q2") (pin "1") (pinfunction "E_1") (pintype "passive"))
      (node (ref "Q3") (pin "1") (pinfunction "E_1") (pintype "passive"))
      (node (ref "Q4") (pin "1") (pinfunction "S_1") (pintype "passive"))
      (node (ref "R7") (pin "2") (pinfunction "2_2") (pintype "passive"))
      (node (ref "R8") (pin "1") (pinfunction "1_1") (pintype "passive"))
      (node (ref "R9") (pin "1") (pinfunction "1_1") (pintype "passive"))
      (node (ref "U1") (pin "1") (pinfunction "GND_1") (pintype "power_in"))
      (node (ref "U10") (pin "1") (pinfunction "G_1") (pintype "input"))
      (node (ref "U16") (pin "11") (pinfunction "A_11") (pintype "input"))
      (node (ref "U16") (pin "13") (pinfunction "A_13") (pintype "input"))
      (node (ref "U16") (pin "15") (pinfunction "A_15") (pintype "input"))
      (node (ref "U16") (pin "17") (pinfunction "A_17") (pintype "input"))
      (node (ref "U16") (pin "2") (pinfunction "A_2") (pintype "input"))
      (node (ref "U16") (pin "6") (pinfunction "A_6") (pintype "input"))
      (node (ref "U16") (pin "8") (pinfunction "A_8") (pintype "input"))
      (node (ref "U17") (pin "17") (pinfunction "A_17") (pintype "input"))
      (node (ref "U17") (pin "2") (pinfunction "A_2") (pintype "input"))
      (node (ref "U17") (pin "4") (pinfunction "A_4") (pintype "input"))
      (node (ref "U19") (pin "8") (pinfunction "A_8") (pintype "input"))
      (node (ref "U20") (pin "5") (pinfunction "G_5") (pintype "input"))
      (node (ref "U20") (pin "6") (pinfunction "H_6") (pintype "input"))
      (node (ref "U22") (pin "1") (pinfunction "~{OE}_1") (pintype "input"))
      (node (ref "U22") (pin "19") (pinfunction "~{OE}_19") (pintype "input"))
      (node (ref "U24") (pin "3") (pinfunction "0V_3") (pintype "input"))
      (node (ref "U26") (pin "21") (pinfunction "IOW_21") (pintype "input"))
      (node (ref "U26") (pin "25") (pinfunction "IOR_25") (pintype "input"))
      (node (ref "U26") (pin "28") (pinfunction "~{AS}_28") (pintype "input"))
      (node (ref "U27") (pin "21") (pinfunction "IOW_21") (pintype "input"))
      (node (ref "U27") (pin "25") (pinfunction "IOR_25") (pintype "input"))
      (node (ref "U27") (pin "28") (pinfunction "~{AS}_28") (pintype "input"))
      (node (ref "U28") (pin "11") (pinfunction "0V_11") (pintype "power_in"))
      (node (ref "U29") (pin "11") (pinfunction "0V_11") (pintype "power_in"))
      (node (ref "Y1") (pin "4") (pinfunction "0V_4") (pintype "power_in"))
    )
    (net (code "53") (name "A0") (class "Default")
      (node (ref "U22") (pin "5") (pinfunction "Y_5") (pintype "tri_state"))
      (node (ref "U26") (pin "31") (pinfunction "A0_31") (pintype "input"))
      (node (ref "U27") (pin "31") (pinfunction "A0_31") (pintype "input"))
      (node (ref "U8") (pin "1") (pinfunction "A_1") (pintype "input"))
      (node (ref "U9") (pin "1") (pinfunction "A_1") (pintype "input"))
    )
    (net (code "54") (name "A1") (class "Default")
      (node (ref "U22") (pin "14") (pinfunction "Y_14") (pintype "tri_state"))
      (node (ref "U26") (pin "30") (pinfunction "A1_30") (pintype "input"))
      (node (ref "U27") (pin "30") (pinfunction "A1_30") (pintype "input"))
      (node (ref "U8") (pin "2") (pinfunction "B_2") (pintype "input"))
      (node (ref "U9") (pin "2") (pinfunction "B_2") (pintype "input"))
    )
    (net (code "55") (name "A2") (class "Default")
      (node (ref "U22") (pin "7") (pinfunction "Y_7") (pintype "tri_state"))
      (node (ref "U26") (pin "29") (pinfunction "A2_29") (pintype "input"))
      (node (ref "U27") (pin "29") (pinfunction "A2_29") (pintype "input"))
      (node (ref "U8") (pin "3") (pinfunction "C_3") (pintype "input"))
      (node (ref "U9") (pin "3") (pinfunction "C_3") (pintype "input"))
    )
    (net (code "56") (name "A3") (class "Default")
      (node (ref "U22") (pin "12") (pinfunction "Y_12") (pintype "tri_state"))
      (node (ref "U23") (pin "1") (pinfunction "I_1") (pintype "input"))
      (node (ref "U27") (pin "14") (pinfunction "CS0_14") (pintype "input"))
    )
    (net (code "57") (name "A4") (class "Default")
      (node (ref "U22") (pin "9") (pinfunction "Y_9") (pintype "tri_state"))
      (node (ref "U23") (pin "3") (pinfunction "I_3") (pintype "input"))
      (node (ref "U8") (pin "6") (pinfunction "G1_6") (pintype "input"))
      (node (ref "U9") (pin "6") (pinfunction "G1_6") (pintype "input"))
    )
    (net (code "58") (name "BA0") (class "Default")
      (node (ref "P1") (pin "22") (pinfunction "A0_22") (pintype "bidirectional"))
      (node (ref "U22") (pin "15") (pinfunction "A_15") (pintype "input"))
    )
    (net (code "59") (name "BA1") (class "Default")
      (node (ref "P1") (pin "23") (pinfunction "A1_23") (pintype "bidirectional"))
      (node (ref "U22") (pin "6") (pinfunction "A_6") (pintype "input"))
    )
    (net (code "60") (name "BA2") (class "Default")
      (node (ref "P1") (pin "24") (pinfunction "A2_24") (pintype "bidirectional"))
      (node (ref "U22") (pin "13") (pinfunction "A_13") (pintype "input"))
    )
    (net (code "61") (name "BA3") (class "Default")
      (node (ref "P1") (pin "25") (pinfunction "A3_25") (pintype "bidirectional"))
      (node (ref "U22") (pin "8") (pinfunction "A_8") (pintype "input"))
    )
    (net (code "62") (name "BA4") (class "Default")
      (node (ref "P1") (pin "26") (pinfunction "A4_26") (pintype "bidirectional"))
      (node (ref "U22") (pin "11") (pinfunction "A_11") (pintype "input"))
    )
    (net (code "63") (name "BUFF_KB_CLOCK") (class "Default")
      (node (ref "U12") (pin "8") (pinfunction "CLK_8") (pintype "input"))
      (node (ref "U13") (pin "8") (pinfunction "CLK_8") (pintype "input"))
      (node (ref "U15") (pin "8") (pinfunction "O_8") (pintype "output"))
      (node (ref "U20") (pin "2") (pinfunction "CLK_2") (pintype "input"))
      (node (ref "U21") (pin "2") (pinfunction "CLK_2") (pintype "input"))
      (node (ref "U4") (pin "11") (pinfunction "I_11") (pintype "input"))
      (node (ref "U5") (pin "11") (pinfunction "CLK_11") (pintype "input"))
    )
    (net (code "64") (name "CGND") (class "Default")
      (node (ref "J1") (pin "S1") (pinfunction "S_S1") (pintype "passive"))
      (node (ref "J1") (pin "S2") (pinfunction "S_S2") (pintype "passive"))
      (node (ref "J2") (pin "S1") (pinfunction "S_S1") (pintype "passive"))
      (node (ref "J2") (pin "S2") (pinfunction "S_S2") (pintype "passive"))
      (node (ref "J3") (pin "G$1") (pinfunction "SHIELD_G$1") (pintype "bidirectional"))
      (node (ref "J3") (pin "G$2") (pinfunction "SHIELD_G$2") (pintype "bidirectional"))
      (node (ref "J3") (pin "G$3") (pinfunction "SHIELD_G$3") (pintype "bidirectional"))
      (node (ref "JP4") (pin "2") (pinfunction "2_2") (pintype "passive"))
    )
    (net (code "65") (name "D0") (class "Default")
      (node (ref "RN3") (pin "2") (pinfunction "2_2") (pintype "passive"))
      (node (ref "U16") (pin "18") (pinfunction "Y_18") (pintype "tri_state"))
      (node (ref "U17") (pin "18") (pinfunction "Y_18") (pintype "tri_state"))
      (node (ref "U18") (pin "18") (pinfunction "Y_18") (pintype "tri_state"))
      (node (ref "U19") (pin "1") (pinfunction "G_1") (pintype "input"))
      (node (ref "U20") (pin "4") (pinfunction "F_4") (pintype "input"))
      (node (ref "U25") (pin "18") (pinfunction "B1_18") (pintype "bidirectional"))
      (node (ref "U26") (pin "2") (pinfunction "D0_2") (pintype "tri_state"))
      (node (ref "U27") (pin "2") (pinfunction "D0_2") (pintype "tri_state"))
    )
    (net (code "66") (name "D1") (class "Default")
      (node (ref "RN3") (pin "3") (pinfunction "3_3") (pintype "passive"))
      (node (ref "U16") (pin "3") (pinfunction "Y_3") (pintype "tri_state"))
      (node (ref "U17") (pin "3") (pinfunction "Y_3") (pintype "tri_state"))
      (node (ref "U18") (pin "3") (pinfunction "Y_3") (pintype "tri_state"))
      (node (ref "U19") (pin "13") (pinfunction "F_13") (pintype "input"))
      (node (ref "U20") (pin "3") (pinfunction "E_3") (pintype "input"))
      (node (ref "U25") (pin "17") (pinfunction "B2_17") (pintype "bidirectional"))
      (node (ref "U26") (pin "3") (pinfunction "D1_3") (pintype "tri_state"))
      (node (ref "U27") (pin "3") (pinfunction "D1_3") (pintype "tri_state"))
    )
    (net (code "67") (name "D2") (class "Default")
      (node (ref "RN3") (pin "4") (pinfunction "4_4") (pintype "passive"))
      (node (ref "U16") (pin "16") (pinfunction "Y_16") (pintype "tri_state"))
      (node (ref "U17") (pin "16") (pinfunction "Y_16") (pintype "tri_state"))
      (node (ref "U18") (pin "16") (pinfunction "Y_16") (pintype "tri_state"))
      (node (ref "U19") (pin "2") (pinfunction "H_2") (pintype "input"))
      (node (ref "U20") (pin "14") (pinfunction "D_14") (pintype "input"))
      (node (ref "U25") (pin "16") (pinfunction "B3_16") (pintype "bidirectional"))
      (node (ref "U26") (pin "4") (pinfunction "D2_4") (pintype "tri_state"))
      (node (ref "U27") (pin "4") (pinfunction "D2_4") (pintype "tri_state"))
    )
    (net (code "68") (name "D3") (class "Default")
      (node (ref "RN3") (pin "5") (pinfunction "5_5") (pintype "passive"))
      (node (ref "U16") (pin "5") (pinfunction "Y_5") (pintype "tri_state"))
      (node (ref "U17") (pin "5") (pinfunction "Y_5") (pintype "tri_state"))
      (node (ref "U18") (pin "5") (pinfunction "Y_5") (pintype "tri_state"))
      (node (ref "U19") (pin "12") (pinfunction "E_12") (pintype "input"))
      (node (ref "U20") (pin "13") (pinfunction "C_13") (pintype "input"))
      (node (ref "U25") (pin "15") (pinfunction "B4_15") (pintype "bidirectional"))
      (node (ref "U26") (pin "5") (pinfunction "D3_5") (pintype "tri_state"))
      (node (ref "U27") (pin "5") (pinfunction "D3_5") (pintype "tri_state"))
    )
    (net (code "69") (name "D4") (class "Default")
      (node (ref "RN3") (pin "6") (pinfunction "6_6") (pintype "passive"))
      (node (ref "U16") (pin "14") (pinfunction "Y_14") (pintype "tri_state"))
      (node (ref "U17") (pin "14") (pinfunction "Y_14") (pintype "tri_state"))
      (node (ref "U18") (pin "14") (pinfunction "Y_14") (pintype "tri_state"))
      (node (ref "U19") (pin "11") (pinfunction "D_11") (pintype "input"))
      (node (ref "U20") (pin "12") (pinfunction "B_12") (pintype "input"))
      (node (ref "U25") (pin "14") (pinfunction "B5_14") (pintype "bidirectional"))
      (node (ref "U26") (pin "6") (pinfunction "D4_6") (pintype "tri_state"))
      (node (ref "U27") (pin "6") (pinfunction "D4_6") (pintype "tri_state"))
    )
    (net (code "70") (name "D5") (class "Default")
      (node (ref "RN3") (pin "7") (pinfunction "7_7") (pintype "passive"))
      (node (ref "U16") (pin "7") (pinfunction "Y_7") (pintype "tri_state"))
      (node (ref "U17") (pin "7") (pinfunction "Y_7") (pintype "tri_state"))
      (node (ref "U18") (pin "7") (pinfunction "Y_7") (pintype "tri_state"))
      (node (ref "U19") (pin "4") (pinfunction "I_4") (pintype "input"))
      (node (ref "U20") (pin "11") (pinfunction "A_11") (pintype "input"))
      (node (ref "U25") (pin "13") (pinfunction "B6_13") (pintype "bidirectional"))
      (node (ref "U26") (pin "7") (pinfunction "D5_7") (pintype "tri_state"))
      (node (ref "U27") (pin "7") (pinfunction "D5_7") (pintype "tri_state"))
    )
    (net (code "71") (name "D6") (class "Default")
      (node (ref "RN3") (pin "8") (pinfunction "8_8") (pintype "passive"))
      (node (ref "U16") (pin "12") (pinfunction "Y_12") (pintype "tri_state"))
      (node (ref "U17") (pin "12") (pinfunction "Y_12") (pintype "tri_state"))
      (node (ref "U18") (pin "12") (pinfunction "Y_12") (pintype "tri_state"))
      (node (ref "U19") (pin "10") (pinfunction "C_10") (pintype "input"))
      (node (ref "U21") (pin "6") (pinfunction "H_6") (pintype "input"))
      (node (ref "U25") (pin "12") (pinfunction "B7_12") (pintype "bidirectional"))
      (node (ref "U26") (pin "8") (pinfunction "D6_8") (pintype "tri_state"))
      (node (ref "U27") (pin "8") (pinfunction "D6_8") (pintype "tri_state"))
    )
    (net (code "72") (name "D7") (class "Default")
      (node (ref "RN3") (pin "9") (pinfunction "9_9") (pintype "passive"))
      (node (ref "U16") (pin "9") (pinfunction "Y_9") (pintype "tri_state"))
      (node (ref "U17") (pin "9") (pinfunction "Y_9") (pintype "tri_state"))
      (node (ref "U18") (pin "9") (pinfunction "Y_9") (pintype "tri_state"))
      (node (ref "U19") (pin "9") (pinfunction "B_9") (pintype "input"))
      (node (ref "U21") (pin "5") (pinfunction "G_5") (pintype "input"))
      (node (ref "U25") (pin "11") (pinfunction "B8_11") (pintype "bidirectional"))
      (node (ref "U26") (pin "9") (pinfunction "D7_9") (pintype "tri_state"))
      (node (ref "U27") (pin "9") (pinfunction "D7_9") (pintype "tri_state"))
    )
    (net (code "73") (name "INT_KB") (class "Default")
      (node (ref "JP3") (pin "1") (pinfunction "1_1") (pintype "passive"))
      (node (ref "U7") (pin "11") (pinfunction "O_11") (pintype "output"))
    )
    (net (code "74") (name "INT_UART1") (class "Default")
      (node (ref "JP1") (pin "1") (pinfunction "1_1") (pintype "passive"))
      (node (ref "U17") (pin "11") (pinfunction "A_11") (pintype "input"))
      (node (ref "U26") (pin "33") (pinfunction "INT_33") (pintype "output"))
    )
    (net (code "75") (name "INT_UART2") (class "Default")
      (node (ref "JP2") (pin "1") (pinfunction "1_1") (pintype "passive"))
      (node (ref "U17") (pin "8") (pinfunction "A_8") (pintype "input"))
      (node (ref "U27") (pin "33") (pinfunction "INT_33") (pintype "output"))
    )
    (net (code "76") (name "KB_CLOCK") (class "Default")
      (node (ref "J3") (pin "5") (pinfunction "5_5") (pintype "bidirectional"))
      (node (ref "Q1") (pin "3") (pinfunction "C_3") (pintype "passive"))
      (node (ref "Q2") (pin "3") (pinfunction "C_3") (pintype "passive"))
      (node (ref "R1") (pin "1") (pinfunction "1_1") (pintype "passive"))
      (node (ref "TP2") (pin "1") (pinfunction "1_1") (pintype "passive"))
      (node (ref "U15") (pin "11") (pinfunction "I_11") (pintype "input"))
    )
    (net (code "77") (name "KB_DATA") (class "Default")
      (node (ref "J3") (pin "1") (pinfunction "1_1") (pintype "bidirectional"))
      (node (ref "Q3") (pin "3") (pinfunction "C_3") (pintype "passive"))
      (node (ref "R5") (pin "1") (pinfunction "1_1") (pintype "passive"))
      (node (ref "TP1") (pin "1") (pinfunction "1_1") (pintype "passive"))
      (node (ref "U15") (pin "13") (pinfunction "I_13") (pintype "input"))
    )
    (net (code "78") (name "KB_DR") (class "Default")
      (node (ref "R3") (pin "1") (pinfunction "1_1") (pintype "passive"))
      (node (ref "U14") (pin "1") (pinfunction "CLR_1") (pintype "input"))
      (node (ref "U14") (pin "9") (pinfunction "Q_9") (pintype "output"))
      (node (ref "U17") (pin "13") (pinfunction "A_13") (pintype "input"))
      (node (ref "U7") (pin "12") (pinfunction "I0_12") (pintype "input"))
    )
    (net (code "79") (name "KB_ERR") (class "Default")
      (node (ref "U17") (pin "6") (pinfunction "A_6") (pintype "input"))
      (node (ref "U2") (pin "3") (pinfunction "O_3") (pintype "output"))
    )
    (net (code "80") (name "KB_WRCYCLE") (class "Default")
      (node (ref "U17") (pin "15") (pinfunction "A_15") (pintype "input"))
      (node (ref "U3") (pin "10") (pinfunction "I1_10") (pintype "input"))
      (node (ref "U5") (pin "5") (pinfunction "Q_5") (pintype "output"))
      (node (ref "U6") (pin "11") (pinfunction "CLK_11") (pintype "input"))
      (node (ref "U7") (pin "10") (pinfunction "I1_10") (pintype "input"))
    )
    (net (code "81") (name "Net-(P1-D0)") (class "Default")
      (node (ref "P1") (pin "43") (pinfunction "D0_43") (pintype "bidirectional"))
      (node (ref "RN2") (pin "1") (pinfunction "1_1") (pintype "passive"))
    )
    (net (code "82") (name "Net-(P1-D1)") (class "Default")
      (node (ref "P1") (pin "44") (pinfunction "D1_44") (pintype "bidirectional"))
      (node (ref "RN1") (pin "1") (pinfunction "1_1") (pintype "passive"))
    )
    (net (code "83") (name "Net-(P1-D2)") (class "Default")
      (node (ref "P1") (pin "45") (pinfunction "D2_45") (pintype "bidirectional"))
      (node (ref "RN2") (pin "3") (pinfunction "1_3") (pintype "passive"))
    )
    (net (code "84") (name "Net-(P1-D3)") (class "Default")
      (node (ref "P1") (pin "46") (pinfunction "D3_46") (pintype "bidirectional"))
      (node (ref "RN1") (pin "3") (pinfunction "1_3") (pintype "passive"))
    )
    (net (code "85") (name "Net-(P1-D4)") (class "Default")
      (node (ref "P1") (pin "47") (pinfunction "D4_47") (pintype "bidirectional"))
      (node (ref "RN2") (pin "5") (pinfunction "1_5") (pintype "passive"))
    )
    (net (code "86") (name "Net-(P1-D5)") (class "Default")
      (node (ref "P1") (pin "48") (pinfunction "D5_48") (pintype "bidirectional"))
      (node (ref "RN1") (pin "5") (pinfunction "1_5") (pintype "passive"))
    )
    (net (code "87") (name "Net-(P1-D6)") (class "Default")
      (node (ref "P1") (pin "49") (pinfunction "D6_49") (pintype "bidirectional"))
      (node (ref "RN2") (pin "7") (pinfunction "1_7") (pintype "passive"))
    )
    (net (code "88") (name "Net-(P1-D7)") (class "Default")
      (node (ref "P1") (pin "50") (pinfunction "D7_50") (pintype "bidirectional"))
      (node (ref "RN1") (pin "7") (pinfunction "1_7") (pintype "passive"))
    )
    (net (code "89") (name "Net-(P1-~{RST})") (class "Default")
      (node (ref "P1") (pin "10") (pinfunction "~{RST}_10") (pintype "bidirectional"))
      (node (ref "U15") (pin "5") (pinfunction "I_5") (pintype "input"))
    )
    (net (code "90") (name "Net-(Q1-B)") (class "Default")
      (node (ref "Q1") (pin "2") (pinfunction "B_2") (pintype "passive"))
      (node (ref "R2") (pin "2") (pinfunction "2_2") (pintype "passive"))
    )
    (net (code "91") (name "Net-(Q2-B)") (class "Default")
      (node (ref "Q2") (pin "2") (pinfunction "B_2") (pintype "passive"))
      (node (ref "R3") (pin "2") (pinfunction "2_2") (pintype "passive"))
    )
    (net (code "92") (name "Net-(Q3-B)") (class "Default")
      (node (ref "Q3") (pin "2") (pinfunction "B_2") (pintype "passive"))
      (node (ref "R4") (pin "2") (pinfunction "2_2") (pintype "passive"))
    )
    (net (code "93") (name "Net-(Q4-G)") (class "Default")
      (node (ref "Q4") (pin "2") (pinfunction "G_2") (pintype "passive"))
      (node (ref "R10") (pin "2") (pinfunction "2_2") (pintype "passive"))
    )
    (net (code "94") (name "Net-(RN1B-2)") (class "Default")
      (node (ref "RN1") (pin "4") (pinfunction "2_4") (pintype "passive"))
      (node (ref "U25") (pin "5") (pinfunction "A4_5") (pintype "bidirectional"))
    )
    (net (code "95") (name "Net-(RN1C-2)") (class "Default")
      (node (ref "RN1") (pin "6") (pinfunction "2_6") (pintype "passive"))
      (node (ref "U25") (pin "7") (pinfunction "A6_7") (pintype "bidirectional"))
    )
    (net (code "96") (name "Net-(RN1D-2)") (class "Default")
      (node (ref "RN1") (pin "8") (pinfunction "2_8") (pintype "passive"))
      (node (ref "U25") (pin "9") (pinfunction "A8_9") (pintype "bidirectional"))
    )
    (net (code "97") (name "Net-(RN2B-2)") (class "Default")
      (node (ref "RN2") (pin "4") (pinfunction "2_4") (pintype "passive"))
      (node (ref "U25") (pin "4") (pinfunction "A3_4") (pintype "bidirectional"))
    )
    (net (code "98") (name "Net-(RN2C-2)") (class "Default")
      (node (ref "RN2") (pin "6") (pinfunction "2_6") (pintype "passive"))
      (node (ref "U25") (pin "6") (pinfunction "A5_6") (pintype "bidirectional"))
    )
    (net (code "99") (name "Net-(RN2D-2)") (class "Default")
      (node (ref "RN2") (pin "8") (pinfunction "2_8") (pintype "passive"))
      (node (ref "U25") (pin "8") (pinfunction "A7_8") (pintype "bidirectional"))
    )
    (net (code "100") (name "Net-(U1-CON)") (class "Default")
      (node (ref "C30") (pin "1") (pinfunction "1_1") (pintype "passive"))
      (node (ref "U1") (pin "5") (pinfunction "CON_5") (pintype "input"))
    )
    (net (code "101") (name "Net-(U1-DIS)") (class "Default")
      (node (ref "C31") (pin "1") (pinfunction "1_1") (pintype "passive"))
      (node (ref "R6") (pin "2") (pinfunction "2_2") (pintype "passive"))
      (node (ref "U1") (pin "6") (pinfunction "TRE_6") (pintype "input"))
      (node (ref "U1") (pin "7") (pinfunction "DIS_7") (pintype "input"))
    )
    (net (code "102") (name "Net-(U1-OUT)") (class "Default")
      (node (ref "R2") (pin "1") (pinfunction "1_1") (pintype "passive"))
      (node (ref "U1") (pin "3") (pinfunction "OUT_3") (pintype "output"))
      (node (ref "U4") (pin "13") (pinfunction "I_13") (pintype "input"))
    )
    (net (code "103") (name "Net-(U1-TRI)") (class "Default")
      (node (ref "U1") (pin "2") (pinfunction "TRI_2") (pintype "input"))
      (node (ref "U6") (pin "8") (pinfunction "~{Q}_8") (pintype "output"))
    )
    (net (code "104") (name "Net-(U2A-I0)") (class "Default")
      (node (ref "U2") (pin "1") (pinfunction "I0_1") (pintype "input"))
      (node (ref "U6") (pin "5") (pinfunction "Q_5") (pintype "output"))
    )
    (net (code "105") (name "Net-(U3A-I2)") (class "Default")
      (node (ref "U3") (pin "13") (pinfunction "I2_13") (pintype "input"))
      (node (ref "U4") (pin "2") (pinfunction "O_2") (pintype "output"))
    )
    (net (code "106") (name "Net-(U3A-O)") (class "Default")
      (node (ref "R10") (pin "1") (pinfunction "1_1") (pintype "passive"))
      (node (ref "U3") (pin "12") (pinfunction "O_12") (pintype "output"))
    )
    (net (code "107") (name "Net-(U3B-I1)") (class "Default")
      (node (ref "U3") (pin "4") (pinfunction "I1_4") (pintype "input"))
      (node (ref "U4") (pin "4") (pinfunction "O_4") (pintype "output"))
      (node (ref "U7") (pin "2") (pinfunction "I1_2") (pintype "input"))
    )
    (net (code "108") (name "Net-(U3B-I2)") (class "Default")
      (node (ref "U3") (pin "5") (pinfunction "I2_5") (pintype "input"))
      (node (ref "U4") (pin "10") (pinfunction "O_10") (pintype "output"))
    )
    (net (code "109") (name "Net-(U3B-O)") (class "Default")
      (node (ref "U3") (pin "6") (pinfunction "O_6") (pintype "output"))
      (node (ref "U4") (pin "5") (pinfunction "I_5") (pintype "input"))
    )
    (net (code "110") (name "Net-(U3C-O)") (class "Default")
      (node (ref "U3") (pin "8") (pinfunction "O_8") (pintype "output"))
      (node (ref "U5") (pin "12") (pinfunction "D_12") (pintype "input"))
    )
    (net (code "111") (name "Net-(U4A-I)") (class "Default")
      (node (ref "JP3") (pin "2") (pinfunction "2_2") (pintype "passive"))
      (node (ref "R7") (pin "1") (pinfunction "1_1") (pintype "passive"))
      (node (ref "U4") (pin "1") (pinfunction "I_1") (pintype "input"))
    )
    (net (code "112") (name "Net-(U4F-O)") (class "Default")
      (node (ref "U4") (pin "12") (pinfunction "O_12") (pintype "output"))
      (node (ref "U6") (pin "13") (pinfunction "CLR_13") (pintype "input"))
    )
    (net (code "113") (name "Net-(U5A-CLR)") (class "Default")
      (node (ref "U5") (pin "1") (pinfunction "CLR_1") (pintype "input"))
      (node (ref "U5") (pin "9") (pinfunction "Q_9") (pintype "output"))
    )
    (net (code "114") (name "Net-(U7C-O)") (class "Default")
      (node (ref "R4") (pin "1") (pinfunction "1_1") (pintype "passive"))
      (node (ref "U7") (pin "8") (pinfunction "O_8") (pintype "output"))
    )
    (net (code "115") (name "Net-(U9A-Y1)") (class "Default")
      (node (ref "U17") (pin "1") (pinfunction "~{OE}_1") (pintype "input"))
      (node (ref "U17") (pin "19") (pinfunction "~{OE}_19") (pintype "input"))
      (node (ref "U9") (pin "14") (pinfunction "Y1_14") (pintype "output"))
    )
    (net (code "116") (name "Net-(U9A-Y7)") (class "Default")
      (node (ref "U16") (pin "1") (pinfunction "~{OE}_1") (pintype "input"))
      (node (ref "U16") (pin "19") (pinfunction "~{OE}_19") (pintype "input"))
      (node (ref "U9") (pin "7") (pinfunction "Y7_7") (pintype "output"))
    )
    (net (code "117") (name "Net-(U10A-A)") (class "Default")
      (node (ref "U10") (pin "8") (pinfunction "A_8") (pintype "input"))
      (node (ref "U11") (pin "9") (pinfunction "Q4_9") (pintype "output"))
      (node (ref "U18") (pin "6") (pinfunction "A_6") (pintype "input"))
    )
    (net (code "118") (name "Net-(U10A-B)") (class "Default")
      (node (ref "U10") (pin "9") (pinfunction "B_9") (pintype "input"))
      (node (ref "U11") (pin "12") (pinfunction "Q5_12") (pintype "output"))
      (node (ref "U18") (pin "15") (pinfunction "A_15") (pintype "input"))
    )
    (net (code "119") (name "Net-(U10A-C)") (class "Default")
      (node (ref "U10") (pin "10") (pinfunction "C_10") (pintype "input"))
      (node (ref "U11") (pin "15") (pinfunction "Q6_15") (pintype "output"))
      (node (ref "U18") (pin "4") (pinfunction "A_4") (pintype "input"))
    )
    (net (code "120") (name "Net-(U10A-D)") (class "Default")
      (node (ref "U10") (pin "11") (pinfunction "D_11") (pintype "input"))
      (node (ref "U11") (pin "6") (pinfunction "Q3_6") (pintype "output"))
      (node (ref "U18") (pin "13") (pinfunction "A_13") (pintype "input"))
    )
    (net (code "121") (name "Net-(U10A-E)") (class "Default")
      (node (ref "U10") (pin "12") (pinfunction "E_12") (pintype "input"))
      (node (ref "U11") (pin "5") (pinfunction "Q2_5") (pintype "output"))
      (node (ref "U18") (pin "8") (pinfunction "A_8") (pintype "input"))
    )
    (net (code "122") (name "Net-(U10A-F)") (class "Default")
      (node (ref "U10") (pin "13") (pinfunction "F_13") (pintype "input"))
      (node (ref "U11") (pin "19") (pinfunction "Q8_19") (pintype "output"))
      (node (ref "U18") (pin "2") (pinfunction "A_2") (pintype "input"))
    )
    (net (code "123") (name "Net-(U10A-H)") (class "Default")
      (node (ref "U10") (pin "2") (pinfunction "H_2") (pintype "input"))
      (node (ref "U11") (pin "2") (pinfunction "Q1_2") (pintype "output"))
      (node (ref "U18") (pin "11") (pinfunction "A_11") (pintype "input"))
    )
    (net (code "124") (name "Net-(U10A-I)") (class "Default")
      (node (ref "U10") (pin "4") (pinfunction "I_4") (pintype "input"))
      (node (ref "U11") (pin "16") (pinfunction "Q7_16") (pintype "output"))
      (node (ref "U18") (pin "17") (pinfunction "A_17") (pintype "input"))
    )
    (net (code "125") (name "Net-(U10A-SOD)") (class "Default")
      (node (ref "U10") (pin "6") (pinfunction "SOD_6") (pintype "output"))
      (node (ref "U2") (pin "2") (pinfunction "I1_2") (pintype "input"))
    )
    (net (code "126") (name "Net-(U11A-CLK)") (class "Default")
      (node (ref "U11") (pin "11") (pinfunction "CLK_11") (pintype "input"))
      (node (ref "U4") (pin "6") (pinfunction "O_6") (pintype "output"))
      (node (ref "U4") (pin "9") (pinfunction "I_9") (pintype "input"))
      (node (ref "U6") (pin "3") (pinfunction "CLK_3") (pintype "input"))
    )
    (net (code "127") (name "Net-(U11A-D1)") (class "Default")
      (node (ref "U11") (pin "3") (pinfunction "D1_3") (pintype "input"))
      (node (ref "U12") (pin "4") (pinfunction "QB_4") (pintype "output"))
    )
    (net (code "128") (name "Net-(U11A-D2)") (class "Default")
      (node (ref "U11") (pin "4") (pinfunction "D2_4") (pintype "input"))
      (node (ref "U12") (pin "5") (pinfunction "QC_5") (pintype "output"))
    )
    (net (code "129") (name "Net-(U11A-D3)") (class "Default")
      (node (ref "U11") (pin "7") (pinfunction "D3_7") (pintype "input"))
      (node (ref "U12") (pin "6") (pinfunction "QD_6") (pintype "output"))
    )
    (net (code "130") (name "Net-(U11A-D4)") (class "Default")
      (node (ref "U11") (pin "8") (pinfunction "D4_8") (pintype "input"))
      (node (ref "U12") (pin "10") (pinfunction "QE_10") (pintype "output"))
    )
    (net (code "131") (name "Net-(U11A-D5)") (class "Default")
      (node (ref "U11") (pin "13") (pinfunction "D5_13") (pintype "input"))
      (node (ref "U12") (pin "11") (pinfunction "QF_11") (pintype "output"))
    )
    (net (code "132") (name "Net-(U11A-D6)") (class "Default")
      (node (ref "U11") (pin "14") (pinfunction "D6_14") (pintype "input"))
      (node (ref "U12") (pin "12") (pinfunction "QG_12") (pintype "output"))
    )
    (net (code "133") (name "Net-(U11A-D7)") (class "Default")
      (node (ref "U11") (pin "17") (pinfunction "D7_17") (pintype "input"))
      (node (ref "U12") (pin "13") (pinfunction "QH_13") (pintype "output"))
      (node (ref "U13") (pin "1") (pinfunction "A_1") (pintype "input"))
    )
    (net (code "134") (name "Net-(U11A-D8)") (class "Default")
      (node (ref "U11") (pin "18") (pinfunction "D8_18") (pintype "input"))
      (node (ref "U13") (pin "3") (pinfunction "QA_3") (pintype "output"))
    )
    (net (code "135") (name "Net-(U12A-CLR)") (class "Default")
      (node (ref "U12") (pin "9") (pinfunction "CLR_9") (pintype "input"))
      (node (ref "U13") (pin "9") (pinfunction "CLR_9") (pintype "input"))
      (node (ref "U7") (pin "3") (pinfunction "O_3") (pintype "output"))
    )
    (net (code "136") (name "Net-(U12A-QA)") (class "Default")
      (node (ref "U12") (pin "3") (pinfunction "QA_3") (pintype "output"))
      (node (ref "U6") (pin "2") (pinfunction "D_2") (pintype "input"))
    )
    (net (code "137") (name "Net-(U13A-QB)") (class "Default")
      (node (ref "U13") (pin "4") (pinfunction "QB_4") (pintype "output"))
      (node (ref "U3") (pin "3") (pinfunction "I0_3") (pintype "input"))
    )
    (net (code "138") (name "Net-(U13A-QC)") (class "Default")
      (node (ref "U13") (pin "5") (pinfunction "QC_5") (pintype "output"))
      (node (ref "U4") (pin "3") (pinfunction "I_3") (pintype "input"))
    )
    (net (code "139") (name "Net-(U14A-~{Q})") (class "Default")
      (node (ref "U14") (pin "6") (pinfunction "~{Q}_6") (pintype "output"))
      (node (ref "U7") (pin "5") (pinfunction "I1_5") (pintype "input"))
    )
    (net (code "140") (name "Net-(U14B-CLK)") (class "Default")
      (node (ref "U14") (pin "11") (pinfunction "CLK_11") (pintype "input"))
      (node (ref "U4") (pin "8") (pinfunction "O_8") (pintype "output"))
    )
    (net (code "141") (name "Net-(U14B-CLR)") (class "Default")
      (node (ref "U14") (pin "13") (pinfunction "CLR_13") (pintype "input"))
      (node (ref "U7") (pin "6") (pinfunction "O_6") (pintype "output"))
    )
    (net (code "142") (name "Net-(U15B-O)") (class "Default")
      (node (ref "U15") (pin "10") (pinfunction "O_10") (pintype "output"))
      (node (ref "U15") (pin "9") (pinfunction "I_9") (pintype "input"))
    )
    (net (code "143") (name "Net-(U19A-SEV)") (class "Default")
      (node (ref "U19") (pin "5") (pinfunction "SEV_5") (pintype "output"))
      (node (ref "U21") (pin "4") (pinfunction "F_4") (pintype "input"))
    )
    (net (code "144") (name "Net-(U20A-QH)") (class "Default")
      (node (ref "U20") (pin "9") (pinfunction "QH_9") (pintype "output"))
      (node (ref "U3") (pin "11") (pinfunction "I2_11") (pintype "input"))
    )
    (net (code "145") (name "Net-(U20A-SER)") (class "Default")
      (node (ref "U20") (pin "10") (pinfunction "SER_10") (pintype "input"))
      (node (ref "U21") (pin "9") (pinfunction "QH_9") (pintype "output"))
    )
    (net (code "146") (name "Net-(U20A-~{QH})") (class "Default")
      (node (ref "U20") (pin "7") (pinfunction "~{QH}_7") (pintype "output"))
      (node (ref "U7") (pin "9") (pinfunction "I0_9") (pintype "input"))
    )
    (net (code "147") (name "Net-(U23A-O)") (class "Default")
      (node (ref "U23") (pin "2") (pinfunction "O_2") (pintype "output"))
      (node (ref "U26") (pin "14") (pinfunction "CS0_14") (pintype "input"))
    )
    (net (code "148") (name "Net-(U23B-O)") (class "Default")
      (node (ref "U23") (pin "4") (pinfunction "O_4") (pintype "output"))
      (node (ref "U26") (pin "15") (pinfunction "CS1_15") (pintype "input"))
      (node (ref "U27") (pin "15") (pinfunction "CS1_15") (pintype "input"))
    )
    (net (code "149") (name "Net-(U23D-I)") (class "Default")
      (node (ref "JP1") (pin "2") (pinfunction "2_2") (pintype "passive"))
      (node (ref "R8") (pin "2") (pinfunction "2_2") (pintype "passive"))
      (node (ref "U23") (pin "9") (pinfunction "I_9") (pintype "input"))
    )
    (net (code "150") (name "Net-(U23D-O)") (class "Default")
      (node (ref "U23") (pin "8") (pinfunction "O_8") (pintype "output"))
      (node (ref "U3") (pin "1") (pinfunction "I0_1") (pintype "input"))
    )
    (net (code "151") (name "Net-(U23E-I)") (class "Default")
      (node (ref "JP2") (pin "2") (pinfunction "2_2") (pintype "passive"))
      (node (ref "R9") (pin "2") (pinfunction "2_2") (pintype "passive"))
      (node (ref "U23") (pin "11") (pinfunction "I_11") (pintype "input"))
    )
    (net (code "152") (name "Net-(U23E-O)") (class "Default")
      (node (ref "U23") (pin "10") (pinfunction "O_10") (pintype "output"))
      (node (ref "U3") (pin "2") (pinfunction "I1_2") (pintype "input"))
    )
    (net (code "153") (name "Net-(U23F-O)") (class "Default")
      (node (ref "U23") (pin "12") (pinfunction "O_12") (pintype "output"))
      (node (ref "U7") (pin "13") (pinfunction "I1_13") (pintype "input"))
    )
    (net (code "154") (name "Net-(U24-C+)") (class "Default")
      (node (ref "C35") (pin "+") (pinfunction "+_+") (pintype "passive"))
      (node (ref "U24") (pin "2") (pinfunction "C+_2") (pintype "bidirectional"))
    )
    (net (code "155") (name "Net-(U24-C-)") (class "Default")
      (node (ref "C35") (pin "-") (pinfunction "-_-") (pintype "passive"))
      (node (ref "U24") (pin "4") (pinfunction "C-_4") (pintype "bidirectional"))
    )
    (net (code "156") (name "Net-(U25A-A1)") (class "Default")
      (node (ref "RN2") (pin "2") (pinfunction "2_2") (pintype "passive"))
      (node (ref "U25") (pin "2") (pinfunction "A1_2") (pintype "bidirectional"))
    )
    (net (code "157") (name "Net-(U25A-A2)") (class "Default")
      (node (ref "RN1") (pin "2") (pinfunction "2_2") (pintype "passive"))
      (node (ref "U25") (pin "3") (pinfunction "A2_3") (pintype "bidirectional"))
    )
    (net (code "158") (name "Net-(U26A-RCLK)") (class "Default")
      (node (ref "U26") (pin "10") (pinfunction "RCLK_10") (pintype "input"))
      (node (ref "U26") (pin "17") (pinfunction "~{BAUDOUT}_17") (pintype "output"))
    )
    (net (code "159") (name "Net-(U26A-RX)") (class "Default")
      (node (ref "U26") (pin "11") (pinfunction "RX_11") (pintype "input"))
      (node (ref "U28") (pin "17") (pinfunction "RY3_17") (pintype "output"))
    )
    (net (code "160") (name "Net-(U26A-TX)") (class "Default")
      (node (ref "U26") (pin "13") (pinfunction "TX_13") (pintype "output"))
      (node (ref "U28") (pin "15") (pinfunction "DA2_15") (pintype "input"))
    )
    (net (code "161") (name "Net-(U26A-XTAL1)") (class "Default")
      (node (ref "U26") (pin "18") (pinfunction "XTAL1_18") (pintype "input"))
      (node (ref "U27") (pin "18") (pinfunction "XTAL1_18") (pintype "input"))
      (node (ref "Y1") (pin "5") (pinfunction "FO_5") (pintype "output"))
    )
    (net (code "162") (name "Net-(U26A-~{CD})") (class "Default")
      (node (ref "U26") (pin "42") (pinfunction "~{CD}_42") (pintype "input"))
      (node (ref "U28") (pin "19") (pinfunction "RY1_19") (pintype "output"))
    )
    (net (code "163") (name "Net-(U26A-~{CTS})") (class "Default")
      (node (ref "U26") (pin "40") (pinfunction "~{CTS}_40") (pintype "input"))
      (node (ref "U28") (pin "14") (pinfunction "RY4_14") (pintype "output"))
    )
    (net (code "164") (name "Net-(U26A-~{DSR})") (class "Default")
      (node (ref "U26") (pin "41") (pinfunction "~{DSR}_41") (pintype "input"))
      (node (ref "U28") (pin "18") (pinfunction "RY2_18") (pintype "output"))
    )
    (net (code "165") (name "Net-(U26A-~{DTR})") (class "Default")
      (node (ref "U26") (pin "37") (pinfunction "~{DTR}_37") (pintype "output"))
      (node (ref "U28") (pin "13") (pinfunction "DA3_13") (pintype "input"))
    )
    (net (code "166") (name "Net-(U26A-~{RI})") (class "Default")
      (node (ref "U26") (pin "43") (pinfunction "~{RI}_43") (pintype "input"))
      (node (ref "U28") (pin "12") (pinfunction "RY5_12") (pintype "output"))
    )
    (net (code "167") (name "Net-(U26A-~{RTS})") (class "Default")
      (node (ref "U26") (pin "36") (pinfunction "~{RTS}_36") (pintype "output"))
      (node (ref "U28") (pin "16") (pinfunction "DA1_16") (pintype "input"))
    )
    (net (code "168") (name "Net-(U27A-RCLK)") (class "Default")
      (node (ref "U27") (pin "10") (pinfunction "RCLK_10") (pintype "input"))
      (node (ref "U27") (pin "17") (pinfunction "~{BAUDOUT}_17") (pintype "output"))
    )
    (net (code "169") (name "Net-(U27A-RX)") (class "Default")
      (node (ref "U27") (pin "11") (pinfunction "RX_11") (pintype "input"))
      (node (ref "U29") (pin "17") (pinfunction "RY3_17") (pintype "output"))
    )
    (net (code "170") (name "Net-(U27A-TX)") (class "Default")
      (node (ref "U27") (pin "13") (pinfunction "TX_13") (pintype "output"))
      (node (ref "U29") (pin "15") (pinfunction "DA2_15") (pintype "input"))
    )
    (net (code "171") (name "Net-(U27A-~{CD})") (class "Default")
      (node (ref "U27") (pin "42") (pinfunction "~{CD}_42") (pintype "input"))
      (node (ref "U29") (pin "19") (pinfunction "RY1_19") (pintype "output"))
    )
    (net (code "172") (name "Net-(U27A-~{CTS})") (class "Default")
      (node (ref "U27") (pin "40") (pinfunction "~{CTS}_40") (pintype "input"))
      (node (ref "U29") (pin "14") (pinfunction "RY4_14") (pintype "output"))
    )
    (net (code "173") (name "Net-(U27A-~{DSR})") (class "Default")
      (node (ref "U27") (pin "41") (pinfunction "~{DSR}_41") (pintype "input"))
      (node (ref "U29") (pin "18") (pinfunction "RY2_18") (pintype "output"))
    )
    (net (code "174") (name "Net-(U27A-~{DTR})") (class "Default")
      (node (ref "U27") (pin "37") (pinfunction "~{DTR}_37") (pintype "output"))
      (node (ref "U29") (pin "13") (pinfunction "DA3_13") (pintype "input"))
    )
    (net (code "175") (name "Net-(U27A-~{OP1})") (class "Default")
      (node (ref "J4") (pin "3") (pinfunction "3_3") (pintype "passive"))
      (node (ref "U27") (pin "38") (pinfunction "~{OP1}_38") (pintype "output"))
    )
    (net (code "176") (name "Net-(U27A-~{OP2})") (class "Default")
      (node (ref "J4") (pin "2") (pinfunction "2_2") (pintype "passive"))
      (node (ref "U27") (pin "35") (pinfunction "~{OP2}_35") (pintype "output"))
    )
    (net (code "177") (name "Net-(U27A-~{RI})") (class "Default")
      (node (ref "U27") (pin "43") (pinfunction "~{RI}_43") (pintype "input"))
      (node (ref "U29") (pin "12") (pinfunction "RY5_12") (pintype "output"))
    )
    (net (code "178") (name "Net-(U27A-~{RTS})") (class "Default")
      (node (ref "U27") (pin "36") (pinfunction "~{RTS}_36") (pintype "output"))
      (node (ref "U29") (pin "16") (pinfunction "DA1_16") (pintype "input"))
    )
    (net (code "179") (name "Net-(U28-DY1)") (class "Default")
      (node (ref "J1") (pin "7") (pinfunction "7_7") (pintype "passive"))
      (node (ref "U28") (pin "5") (pinfunction "DY1_5") (pintype "output"))
    )
    (net (code "180") (name "Net-(U28-DY2)") (class "Default")
      (node (ref "J1") (pin "3") (pinfunction "3_3") (pintype "passive"))
      (node (ref "U28") (pin "6") (pinfunction "DY2_6") (pintype "output"))
    )
    (net (code "181") (name "Net-(U28-DY3)") (class "Default")
      (node (ref "J1") (pin "4") (pinfunction "4_4") (pintype "passive"))
      (node (ref "U28") (pin "8") (pinfunction "DY3_8") (pintype "output"))
    )
    (net (code "182") (name "Net-(U28-RA1)") (class "Default")
      (node (ref "J1") (pin "1") (pinfunction "1_1") (pintype "passive"))
      (node (ref "U28") (pin "2") (pinfunction "RA1_2") (pintype "input"))
    )
    (net (code "183") (name "Net-(U28-RA2)") (class "Default")
      (node (ref "J1") (pin "6") (pinfunction "6_6") (pintype "passive"))
      (node (ref "U28") (pin "3") (pinfunction "RA2_3") (pintype "input"))
    )
    (net (code "184") (name "Net-(U28-RA3)") (class "Default")
      (node (ref "J1") (pin "2") (pinfunction "2_2") (pintype "passive"))
      (node (ref "U28") (pin "4") (pinfunction "RA3_4") (pintype "input"))
    )
    (net (code "185") (name "Net-(U28-RA4)") (class "Default")
      (node (ref "J1") (pin "8") (pinfunction "8_8") (pintype "passive"))
      (node (ref "U28") (pin "7") (pinfunction "RA4_7") (pintype "input"))
    )
    (net (code "186") (name "Net-(U28-RA5)") (class "Default")
      (node (ref "J1") (pin "9") (pinfunction "9_9") (pintype "passive"))
      (node (ref "U28") (pin "9") (pinfunction "RA5_9") (pintype "input"))
    )
    (net (code "187") (name "Net-(U29-DY1)") (class "Default")
      (node (ref "J2") (pin "7") (pinfunction "7_7") (pintype "passive"))
      (node (ref "U29") (pin "5") (pinfunction "DY1_5") (pintype "output"))
    )
    (net (code "188") (name "Net-(U29-DY2)") (class "Default")
      (node (ref "J2") (pin "3") (pinfunction "3_3") (pintype "passive"))
      (node (ref "U29") (pin "6") (pinfunction "DY2_6") (pintype "output"))
    )
    (net (code "189") (name "Net-(U29-DY3)") (class "Default")
      (node (ref "J2") (pin "4") (pinfunction "4_4") (pintype "passive"))
      (node (ref "U29") (pin "8") (pinfunction "DY3_8") (pintype "output"))
    )
    (net (code "190") (name "Net-(U29-RA1)") (class "Default")
      (node (ref "J2") (pin "1") (pinfunction "1_1") (pintype "passive"))
      (node (ref "U29") (pin "2") (pinfunction "RA1_2") (pintype "input"))
    )
    (net (code "191") (name "Net-(U29-RA2)") (class "Default")
      (node (ref "J2") (pin "6") (pinfunction "6_6") (pintype "passive"))
      (node (ref "U29") (pin "3") (pinfunction "RA2_3") (pintype "input"))
    )
    (net (code "192") (name "Net-(U29-RA3)") (class "Default")
      (node (ref "J2") (pin "2") (pinfunction "2_2") (pintype "passive"))
      (node (ref "U29") (pin "4") (pinfunction "RA3_4") (pintype "input"))
    )
    (net (code "193") (name "Net-(U29-RA4)") (class "Default")
      (node (ref "J2") (pin "8") (pinfunction "8_8") (pintype "passive"))
      (node (ref "U29") (pin "7") (pinfunction "RA4_7") (pintype "input"))
    )
    (net (code "194") (name "Net-(U29-RA5)") (class "Default")
      (node (ref "J2") (pin "9") (pinfunction "9_9") (pintype "passive"))
      (node (ref "U29") (pin "9") (pinfunction "RA5_9") (pintype "input"))
    )
    (net (code "195") (name "RST") (class "Default")
      (node (ref "U15") (pin "1") (pinfunction "I_1") (pintype "input"))
      (node (ref "U15") (pin "6") (pinfunction "O_6") (pintype "output"))
      (node (ref "U26") (pin "39") (pinfunction "RESET_39") (pintype "input"))
      (node (ref "U27") (pin "39") (pinfunction "RESET_39") (pintype "input"))
    )
    (net (code "196") (name "unconnected-(J3-Pad2)") (class "Default")
      (node (ref "J3") (pin "2") (pinfunction "2_2") (pintype "bidirectional"))
    )
    (net (code "197") (name "unconnected-(J3-Pad6)") (class "Default")
      (node (ref "J3") (pin "6") (pinfunction "6_6") (pintype "bidirectional"))
    )
    (net (code "198") (name "unconnected-(P1-+3.3V-Pad2)") (class "Default")
      (node (ref "P1") (pin "2") (pinfunction "+3.3V_2") (pintype "bidirectional"))
    )
    (net (code "199") (name "unconnected-(P1-+5VSB-Pad8)") (class "Default")
      (node (ref "P1") (pin "8") (pinfunction "+5VSB_8") (pintype "bidirectional"))
    )
    (net (code "200") (name "unconnected-(P1--12V-Pad7)") (class "Default")
      (node (ref "P1") (pin "7") (pinfunction "-12V_7") (pintype "bidirectional"))
    )
    (net (code "201") (name "unconnected-(P1-A5-Pad27)") (class "Default")
      (node (ref "P1") (pin "27") (pinfunction "A5_27") (pintype "bidirectional"))
    )
    (net (code "202") (name "unconnected-(P1-A6-Pad28)") (class "Default")
      (node (ref "P1") (pin "28") (pinfunction "A6_28") (pintype "bidirectional"))
    )
    (net (code "203") (name "unconnected-(P1-A7-Pad29)") (class "Default")
      (node (ref "P1") (pin "29") (pinfunction "A7_29") (pintype "bidirectional"))
    )
    (net (code "204") (name "unconnected-(P1-A8-Pad30)") (class "Default")
      (node (ref "P1") (pin "30") (pinfunction "A8_30") (pintype "bidirectional"))
    )
    (net (code "205") (name "unconnected-(P1-A9-Pad31)") (class "Default")
      (node (ref "P1") (pin "31") (pinfunction "A9_31") (pintype "bidirectional"))
    )
    (net (code "206") (name "unconnected-(P1-A10-Pad32)") (class "Default")
      (node (ref "P1") (pin "32") (pinfunction "A10_32") (pintype "bidirectional"))
    )
    (net (code "207") (name "unconnected-(P1-A11-Pad33)") (class "Default")
      (node (ref "P1") (pin "33") (pinfunction "A11_33") (pintype "bidirectional"))
    )
    (net (code "208") (name "unconnected-(P1-A12-Pad34)") (class "Default")
      (node (ref "P1") (pin "34") (pinfunction "A12_34") (pintype "bidirectional"))
    )
    (net (code "209") (name "unconnected-(P1-A13-Pad35)") (class "Default")
      (node (ref "P1") (pin "35") (pinfunction "A13_35") (pintype "bidirectional"))
    )
    (net (code "210") (name "unconnected-(P1-A14-Pad36)") (class "Default")
      (node (ref "P1") (pin "36") (pinfunction "A14_36") (pintype "bidirectional"))
    )
    (net (code "211") (name "unconnected-(P1-A15-Pad37)") (class "Default")
      (node (ref "P1") (pin "37") (pinfunction "A15_37") (pintype "bidirectional"))
    )
    (net (code "212") (name "unconnected-(P1-A16-Pad38)") (class "Default")
      (node (ref "P1") (pin "38") (pinfunction "A16_38") (pintype "bidirectional"))
    )
    (net (code "213") (name "unconnected-(P1-A17-Pad39)") (class "Default")
      (node (ref "P1") (pin "39") (pinfunction "A17_39") (pintype "bidirectional"))
    )
    (net (code "214") (name "unconnected-(P1-A18-Pad40)") (class "Default")
      (node (ref "P1") (pin "40") (pinfunction "A18_40") (pintype "bidirectional"))
    )
    (net (code "215") (name "unconnected-(P1-A19-Pad41)") (class "Default")
      (node (ref "P1") (pin "41") (pinfunction "A19_41") (pintype "bidirectional"))
    )
    (net (code "216") (name "unconnected-(P1-CLK-Pad13)") (class "Default")
      (node (ref "P1") (pin "13") (pinfunction "CLK_13") (pintype "bidirectional"))
    )
    (net (code "217") (name "unconnected-(P1-~{BUSAK}-Pad12)") (class "Default")
      (node (ref "P1") (pin "12") (pinfunction "~{BUSAK}_12") (pintype "bidirectional"))
    )
    (net (code "218") (name "unconnected-(P1-~{BUSRQ}-Pad11)") (class "Default")
      (node (ref "P1") (pin "11") (pinfunction "~{BUSRQ}_11") (pintype "bidirectional"))
    )
    (net (code "219") (name "unconnected-(P1-~{FETCH}-Pad14)") (class "Default")
      (node (ref "P1") (pin "14") (pinfunction "~{FETCH}_14") (pintype "bidirectional"))
    )
    (net (code "220") (name "unconnected-(P1-~{HALT}-Pad15)") (class "Default")
      (node (ref "P1") (pin "15") (pinfunction "~{HALT}_15") (pintype "bidirectional"))
    )
    (net (code "221") (name "unconnected-(P1-~{INH}-Pad17)") (class "Default")
      (node (ref "P1") (pin "17") (pinfunction "~{INH}_17") (pintype "bidirectional"))
    )
    (net (code "222") (name "unconnected-(P1-~{IOSEL}-Pad18)") (class "Default")
      (node (ref "P1") (pin "18") (pinfunction "~{IOSEL}_18") (pintype "bidirectional"))
    )
    (net (code "223") (name "unconnected-(P1-~{NMI}-Pad61)") (class "Default")
      (node (ref "P1") (pin "61") (pinfunction "~{NMI}_61") (pintype "bidirectional"))
    )
    (net (code "224") (name "unconnected-(P1-~{SINT}-Pad51)") (class "Default")
      (node (ref "P1") (pin "51") (pinfunction "~{SINT}_51") (pintype "bidirectional"))
    )
    (net (code "225") (name "unconnected-(P1-~{V0}-Pad53)") (class "Default")
      (node (ref "P1") (pin "53") (pinfunction "~{V0}_53") (pintype "bidirectional"))
    )
    (net (code "226") (name "unconnected-(P1-~{V1}-Pad54)") (class "Default")
      (node (ref "P1") (pin "54") (pinfunction "~{V1}_54") (pintype "bidirectional"))
    )
    (net (code "227") (name "unconnected-(P1-~{V2}-Pad55)") (class "Default")
      (node (ref "P1") (pin "55") (pinfunction "~{V2}_55") (pintype "bidirectional"))
    )
    (net (code "228") (name "unconnected-(P1-~{V3}-Pad56)") (class "Default")
      (node (ref "P1") (pin "56") (pinfunction "~{V3}_56") (pintype "bidirectional"))
    )
    (net (code "229") (name "unconnected-(P1-~{V4}-Pad57)") (class "Default")
      (node (ref "P1") (pin "57") (pinfunction "~{V4}_57") (pintype "bidirectional"))
    )
    (net (code "230") (name "unconnected-(P1-~{V5}-Pad58)") (class "Default")
      (node (ref "P1") (pin "58") (pinfunction "~{V5}_58") (pintype "bidirectional"))
    )
    (net (code "231") (name "unconnected-(P1-~{V6}-Pad59)") (class "Default")
      (node (ref "P1") (pin "59") (pinfunction "~{V6}_59") (pintype "bidirectional"))
    )
    (net (code "232") (name "unconnected-(P1-~{V7}-Pad60)") (class "Default")
      (node (ref "P1") (pin "60") (pinfunction "~{V7}_60") (pintype "bidirectional"))
    )
    (net (code "233") (name "unconnected-(P1-~{WAIT}-Pad16)") (class "Default")
      (node (ref "P1") (pin "16") (pinfunction "~{WAIT}_16") (pintype "bidirectional"))
    )
    (net (code "234") (name "unconnected-(U2B-O-Pad6)") (class "Default")
      (node (ref "U2") (pin "6") (pinfunction "O_6") (pintype "output"))
    )
    (net (code "235") (name "unconnected-(U2C-O-Pad8)") (class "Default")
      (node (ref "U2") (pin "8") (pinfunction "O_8") (pintype "output"))
    )
    (net (code "236") (name "unconnected-(U2D-O-Pad11)") (class "Default")
      (node (ref "U2") (pin "11") (pinfunction "O_11") (pintype "output"))
    )
    (net (code "237") (name "unconnected-(U5B-~{Q}-Pad8)") (class "Default")
      (node (ref "U5") (pin "8") (pinfunction "~{Q}_8") (pintype "output"))
    )
    (net (code "238") (name "unconnected-(U6A-~{Q}-Pad6)") (class "Default")
      (node (ref "U6") (pin "6") (pinfunction "~{Q}_6") (pintype "output"))
    )
    (net (code "239") (name "unconnected-(U6B-Q-Pad9)") (class "Default")
      (node (ref "U6") (pin "9") (pinfunction "Q_9") (pintype "output"))
    )
    (net (code "240") (name "unconnected-(U8A-Y1-Pad14)") (class "Default")
      (node (ref "U8") (pin "14") (pinfunction "Y1_14") (pintype "output"))
    )
    (net (code "241") (name "unconnected-(U8A-Y2-Pad13)") (class "Default")
      (node (ref "U8") (pin "13") (pinfunction "Y2_13") (pintype "output"))
    )
    (net (code "242") (name "unconnected-(U8A-Y3-Pad12)") (class "Default")
      (node (ref "U8") (pin "12") (pinfunction "Y3_12") (pintype "output"))
    )
    (net (code "243") (name "unconnected-(U8A-Y4-Pad11)") (class "Default")
      (node (ref "U8") (pin "11") (pinfunction "Y4_11") (pintype "output"))
    )
    (net (code "244") (name "unconnected-(U8A-Y5-Pad10)") (class "Default")
      (node (ref "U8") (pin "10") (pinfunction "Y5_10") (pintype "output"))
    )
    (net (code "245") (name "unconnected-(U8A-Y6-Pad9)") (class "Default")
      (node (ref "U8") (pin "9") (pinfunction "Y6_9") (pintype "output"))
    )
    (net (code "246") (name "unconnected-(U8A-Y7-Pad7)") (class "Default")
      (node (ref "U8") (pin "7") (pinfunction "Y7_7") (pintype "output"))
    )
    (net (code "247") (name "unconnected-(U9A-Y2-Pad13)") (class "Default")
      (node (ref "U9") (pin "13") (pinfunction "Y2_13") (pintype "output"))
    )
    (net (code "248") (name "unconnected-(U9A-Y3-Pad12)") (class "Default")
      (node (ref "U9") (pin "12") (pinfunction "Y3_12") (pintype "output"))
    )
    (net (code "249") (name "unconnected-(U9A-Y4-Pad11)") (class "Default")
      (node (ref "U9") (pin "11") (pinfunction "Y4_11") (pintype "output"))
    )
    (net (code "250") (name "unconnected-(U9A-Y5-Pad10)") (class "Default")
      (node (ref "U9") (pin "10") (pinfunction "Y5_10") (pintype "output"))
    )
    (net (code "251") (name "unconnected-(U9A-Y6-Pad9)") (class "Default")
      (node (ref "U9") (pin "9") (pinfunction "Y6_9") (pintype "output"))
    )
    (net (code "252") (name "unconnected-(U10A-SEV-Pad5)") (class "Default")
      (node (ref "U10") (pin "5") (pinfunction "SEV_5") (pintype "output"))
    )
    (net (code "253") (name "unconnected-(U13A-QD-Pad6)") (class "Default")
      (node (ref "U13") (pin "6") (pinfunction "QD_6") (pintype "output"))
    )
    (net (code "254") (name "unconnected-(U13A-QE-Pad10)") (class "Default")
      (node (ref "U13") (pin "10") (pinfunction "QE_10") (pintype "output"))
    )
    (net (code "255") (name "unconnected-(U13A-QF-Pad11)") (class "Default")
      (node (ref "U13") (pin "11") (pinfunction "QF_11") (pintype "output"))
    )
    (net (code "256") (name "unconnected-(U13A-QG-Pad12)") (class "Default")
      (node (ref "U13") (pin "12") (pinfunction "QG_12") (pintype "output"))
    )
    (net (code "257") (name "unconnected-(U13A-QH-Pad13)") (class "Default")
      (node (ref "U13") (pin "13") (pinfunction "QH_13") (pintype "output"))
    )
    (net (code "258") (name "unconnected-(U14A-Q-Pad5)") (class "Default")
      (node (ref "U14") (pin "5") (pinfunction "Q_5") (pintype "output"))
    )
    (net (code "259") (name "unconnected-(U14B-~{Q}-Pad8)") (class "Default")
      (node (ref "U14") (pin "8") (pinfunction "~{Q}_8") (pintype "output"))
    )
    (net (code "260") (name "unconnected-(U15E-O-Pad4)") (class "Default")
      (node (ref "U15") (pin "4") (pinfunction "O_4") (pintype "output"))
    )
    (net (code "261") (name "unconnected-(U19A-SOD-Pad6)") (class "Default")
      (node (ref "U19") (pin "6") (pinfunction "SOD_6") (pintype "output"))
    )
    (net (code "262") (name "unconnected-(U21A-~{QH}-Pad7)") (class "Default")
      (node (ref "U21") (pin "7") (pinfunction "~{QH}_7") (pintype "output"))
    )
    (net (code "263") (name "unconnected-(U23C-O-Pad6)") (class "Default")
      (node (ref "U23") (pin "6") (pinfunction "O_6") (pintype "output"))
    )
    (net (code "264") (name "unconnected-(U24-FREQX2-Pad6)") (class "Default")
      (node (ref "U24") (pin "6") (pinfunction "FREQX2_6") (pintype "bidirectional"))
    )
    (net (code "265") (name "unconnected-(U24-OSC-Pad7)") (class "Default")
      (node (ref "U24") (pin "7") (pinfunction "OSC_7") (pintype "bidirectional"))
    )
    (net (code "266") (name "unconnected-(U24-ZC-Pad1)") (class "Default")
      (node (ref "U24") (pin "1") (pinfunction "ZC_1") (pintype "bidirectional"))
    )
    (net (code "267") (name "unconnected-(U26A-XTAL2-Pad19)") (class "Default")
      (node (ref "U26") (pin "19") (pinfunction "XTAL2_19") (pintype "output"))
    )
    (net (code "268") (name "unconnected-(U26A-~{DDIS}-Pad26)") (class "Default")
      (node (ref "U26") (pin "26") (pinfunction "~{DDIS}_26") (pintype "output"))
    )
    (net (code "269") (name "unconnected-(U26A-~{OP2}-Pad35)") (class "Default")
      (node (ref "U26") (pin "35") (pinfunction "~{OP2}_35") (pintype "output"))
    )
    (net (code "270") (name "unconnected-(U26A-~{RXRDY}-Pad32)") (class "Default")
      (node (ref "U26") (pin "32") (pinfunction "~{RXRDY}_32") (pintype "output"))
    )
    (net (code "271") (name "unconnected-(U26A-~{TXRDY}-Pad27)") (class "Default")
      (node (ref "U26") (pin "27") (pinfunction "~{TXRDY}_27") (pintype "output"))
    )
    (net (code "272") (name "unconnected-(U27A-XTAL2-Pad19)") (class "Default")
      (node (ref "U27") (pin "19") (pinfunction "XTAL2_19") (pintype "output"))
    )
    (net (code "273") (name "unconnected-(U27A-~{DDIS}-Pad26)") (class "Default")
      (node (ref "U27") (pin "26") (pinfunction "~{DDIS}_26") (pintype "output"))
    )
    (net (code "274") (name "unconnected-(U27A-~{RXRDY}-Pad32)") (class "Default")
      (node (ref "U27") (pin "32") (pinfunction "~{RXRDY}_32") (pintype "output"))
    )
    (net (code "275") (name "unconnected-(U27A-~{TXRDY}-Pad27)") (class "Default")
      (node (ref "U27") (pin "27") (pinfunction "~{TXRDY}_27") (pintype "output"))
    )
    (net (code "276") (name "~{BCSX}") (class "Default")
      (node (ref "P1") (pin "9") (pinfunction "~{CSX}_9") (pintype "bidirectional"))
      (node (ref "U22") (pin "2") (pinfunction "A_2") (pintype "input"))
    )
    (net (code "277") (name "~{BIRQX}") (class "Default")
      (node (ref "P1") (pin "52") (pinfunction "~{IRQX}_52") (pintype "bidirectional"))
      (node (ref "Q4") (pin "3") (pinfunction "D_3") (pintype "passive"))
    )
    (net (code "278") (name "~{BRD}") (class "Default")
      (node (ref "P1") (pin "19") (pinfunction "~{RD}_19") (pintype "bidirectional"))
      (node (ref "U22") (pin "4") (pinfunction "A_4") (pintype "input"))
    )
    (net (code "279") (name "~{BWR}") (class "Default")
      (node (ref "P1") (pin "20") (pinfunction "~{WR}_20") (pintype "bidirectional"))
      (node (ref "U22") (pin "17") (pinfunction "A_17") (pintype "input"))
    )
    (net (code "280") (name "~{CSX}") (class "Default")
      (node (ref "U22") (pin "18") (pinfunction "Y_18") (pintype "tri_state"))
      (node (ref "U25") (pin "19") (pinfunction "~{OE}_19") (pintype "input"))
      (node (ref "U26") (pin "16") (pinfunction "~{CS2}_16") (pintype "input"))
      (node (ref "U27") (pin "16") (pinfunction "~{CS2}_16") (pintype "input"))
      (node (ref "U8") (pin "4") (pinfunction "G2A_4") (pintype "input"))
      (node (ref "U9") (pin "4") (pinfunction "G2A_4") (pintype "input"))
    )
    (net (code "281") (name "~{CS_KBR}") (class "Default")
      (node (ref "U14") (pin "3") (pinfunction "CLK_3") (pintype "input"))
      (node (ref "U18") (pin "1") (pinfunction "~{OE}_1") (pintype "input"))
      (node (ref "U18") (pin "19") (pinfunction "~{OE}_19") (pintype "input"))
      (node (ref "U9") (pin "15") (pinfunction "Y0_15") (pintype "output"))
    )
    (net (code "282") (name "~{CS_KBW}") (class "Default")
      (node (ref "U20") (pin "1") (pinfunction "SH/~{LD}_1") (pintype "input"))
      (node (ref "U21") (pin "1") (pinfunction "SH/~{LD}_1") (pintype "input"))
      (node (ref "U5") (pin "10") (pinfunction "PRE_10") (pintype "input"))
      (node (ref "U5") (pin "3") (pinfunction "CLK_3") (pintype "input"))
      (node (ref "U8") (pin "15") (pinfunction "Y0_15") (pintype "output"))
    )
    (net (code "283") (name "~{KB_DATA}") (class "Default")
      (node (ref "U12") (pin "1") (pinfunction "A_1") (pintype "input"))
      (node (ref "U15") (pin "12") (pinfunction "O_12") (pintype "output"))
      (node (ref "U3") (pin "9") (pinfunction "I0_9") (pintype "input"))
    )
    (net (code "284") (name "~{KB_INT_ENABLE}") (class "Default")
      (node (ref "U23") (pin "13") (pinfunction "I_13") (pintype "input"))
      (node (ref "U26") (pin "38") (pinfunction "~{OP1}_38") (pintype "output"))
    )
    (net (code "285") (name "~{KB_WRCYCLE}") (class "Default")
      (node (ref "U12") (pin "2") (pinfunction "B_2") (pintype "input"))
      (node (ref "U13") (pin "2") (pinfunction "B_2") (pintype "input"))
      (node (ref "U20") (pin "15") (pinfunction "INH_15") (pintype "input"))
      (node (ref "U21") (pin "15") (pinfunction "INH_15") (pintype "input"))
      (node (ref "U5") (pin "6") (pinfunction "~{Q}_6") (pintype "output"))
    )
    (net (code "286") (name "~{RD}") (class "Default")
      (node (ref "U22") (pin "16") (pinfunction "Y_16") (pintype "tri_state"))
      (node (ref "U25") (pin "1") (pinfunction "DIR_1") (pintype "input"))
      (node (ref "U26") (pin "24") (pinfunction "~{IOR}_24") (pintype "input"))
      (node (ref "U27") (pin "24") (pinfunction "~{IOR}_24") (pintype "input"))
      (node (ref "U9") (pin "5") (pinfunction "G2B_5") (pintype "input"))
    )
    (net (code "287") (name "~{RST}") (class "Default")
      (node (ref "U11") (pin "1") (pinfunction "CLR_1") (pintype "input"))
      (node (ref "U15") (pin "2") (pinfunction "O_2") (pintype "output"))
      (node (ref "U5") (pin "13") (pinfunction "CLR_13") (pintype "input"))
      (node (ref "U6") (pin "1") (pinfunction "CLR_1") (pintype "input"))
      (node (ref "U7") (pin "1") (pinfunction "I0_1") (pintype "input"))
      (node (ref "U7") (pin "4") (pinfunction "I0_4") (pintype "input"))
    )
    (net (code "288") (name "~{WR}") (class "Default")
      (node (ref "U22") (pin "3") (pinfunction "Y_3") (pintype "tri_state"))
      (node (ref "U26") (pin "20") (pinfunction "~{IOW}_20") (pintype "input"))
      (node (ref "U27") (pin "20") (pinfunction "~{IOW}_20") (pintype "input"))
      (node (ref "U8") (pin "5") (pinfunction "G2B_5") (pintype "input"))
    )
  )
)
